# u4xVCA_v3.net
KiCad netlist of a schematic drawn in EAGLE
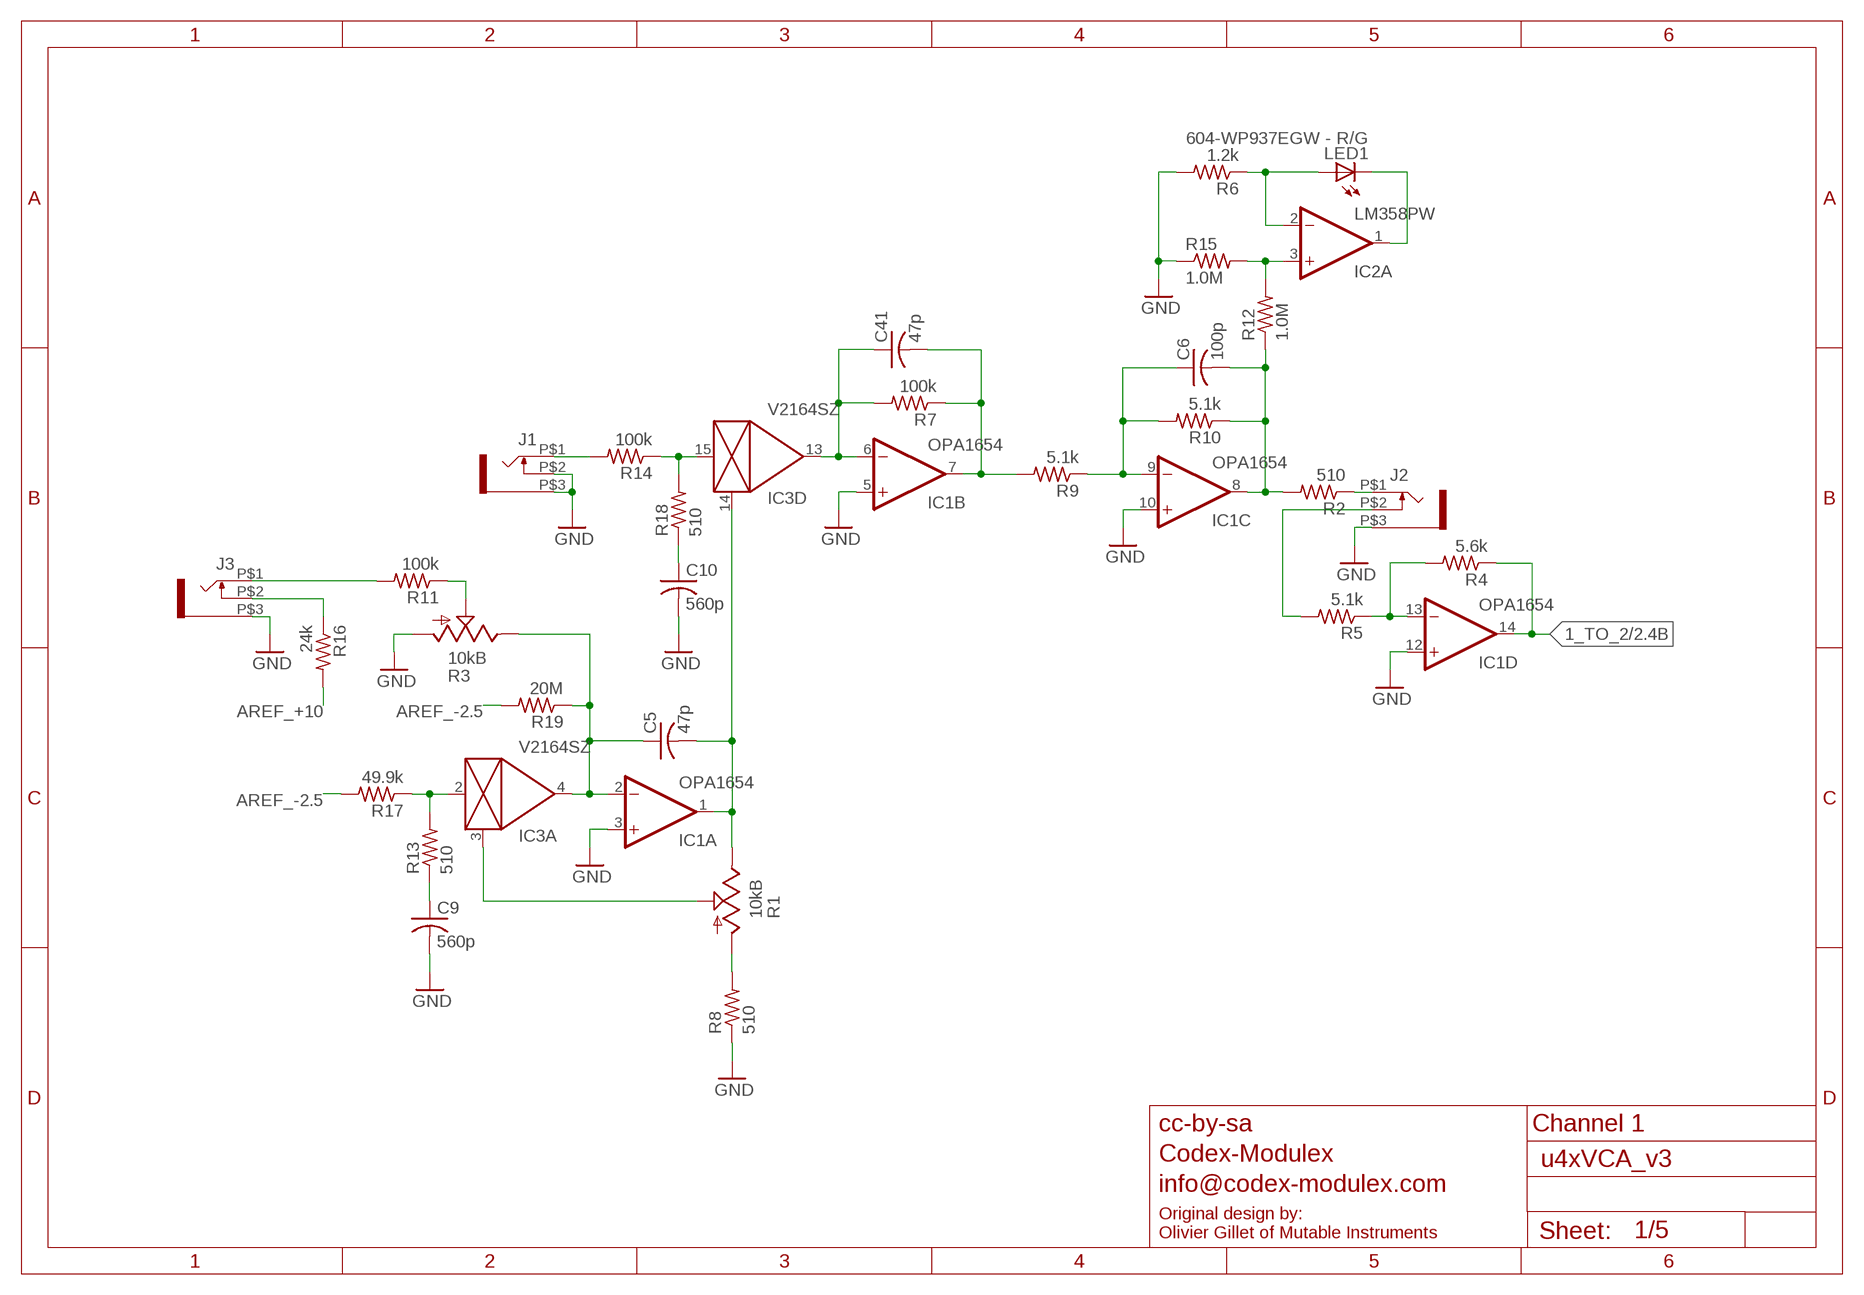
[diagram p0: schematic, sheet 1]
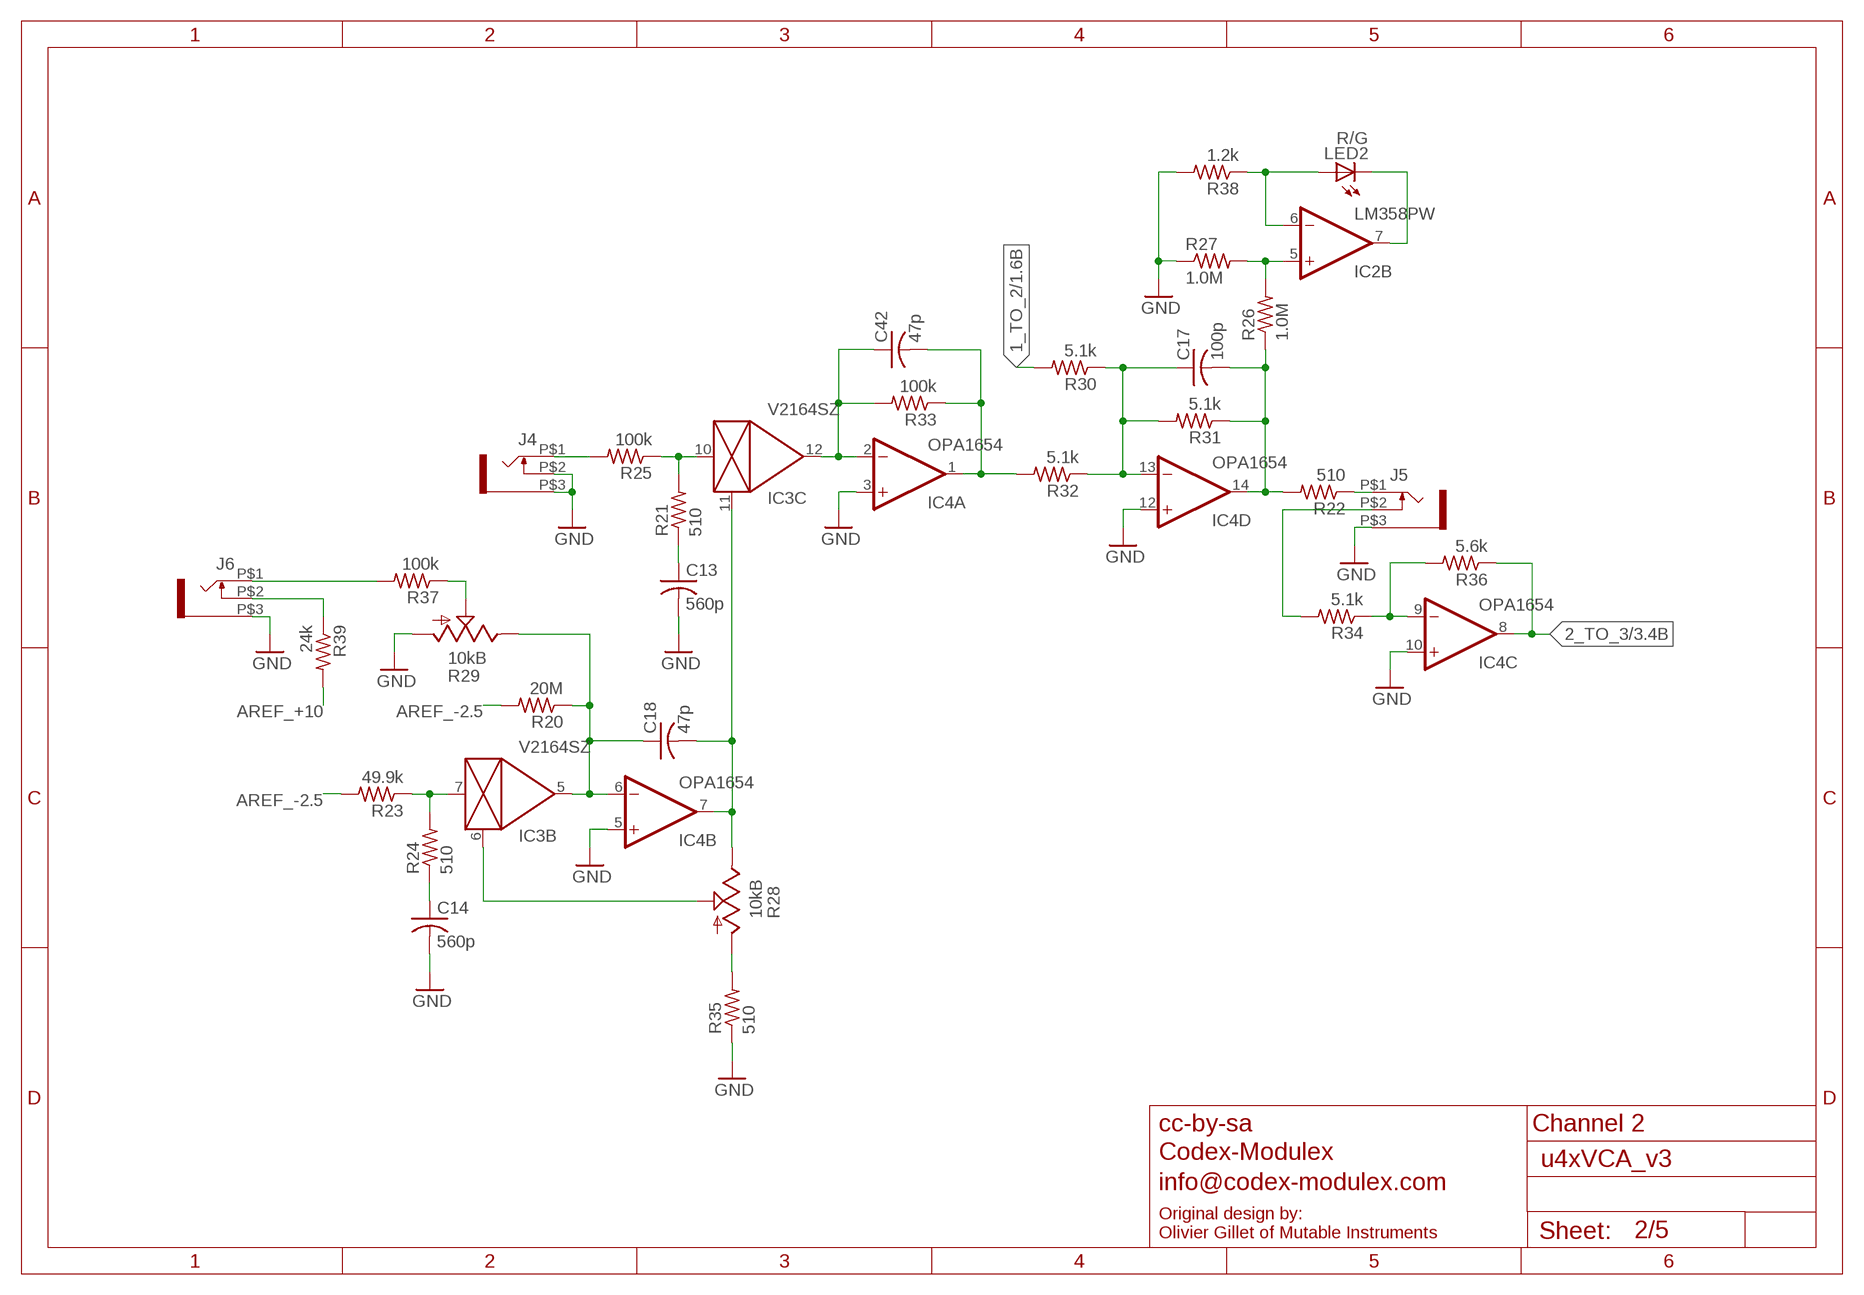
[diagram p1: schematic, sheet 2]
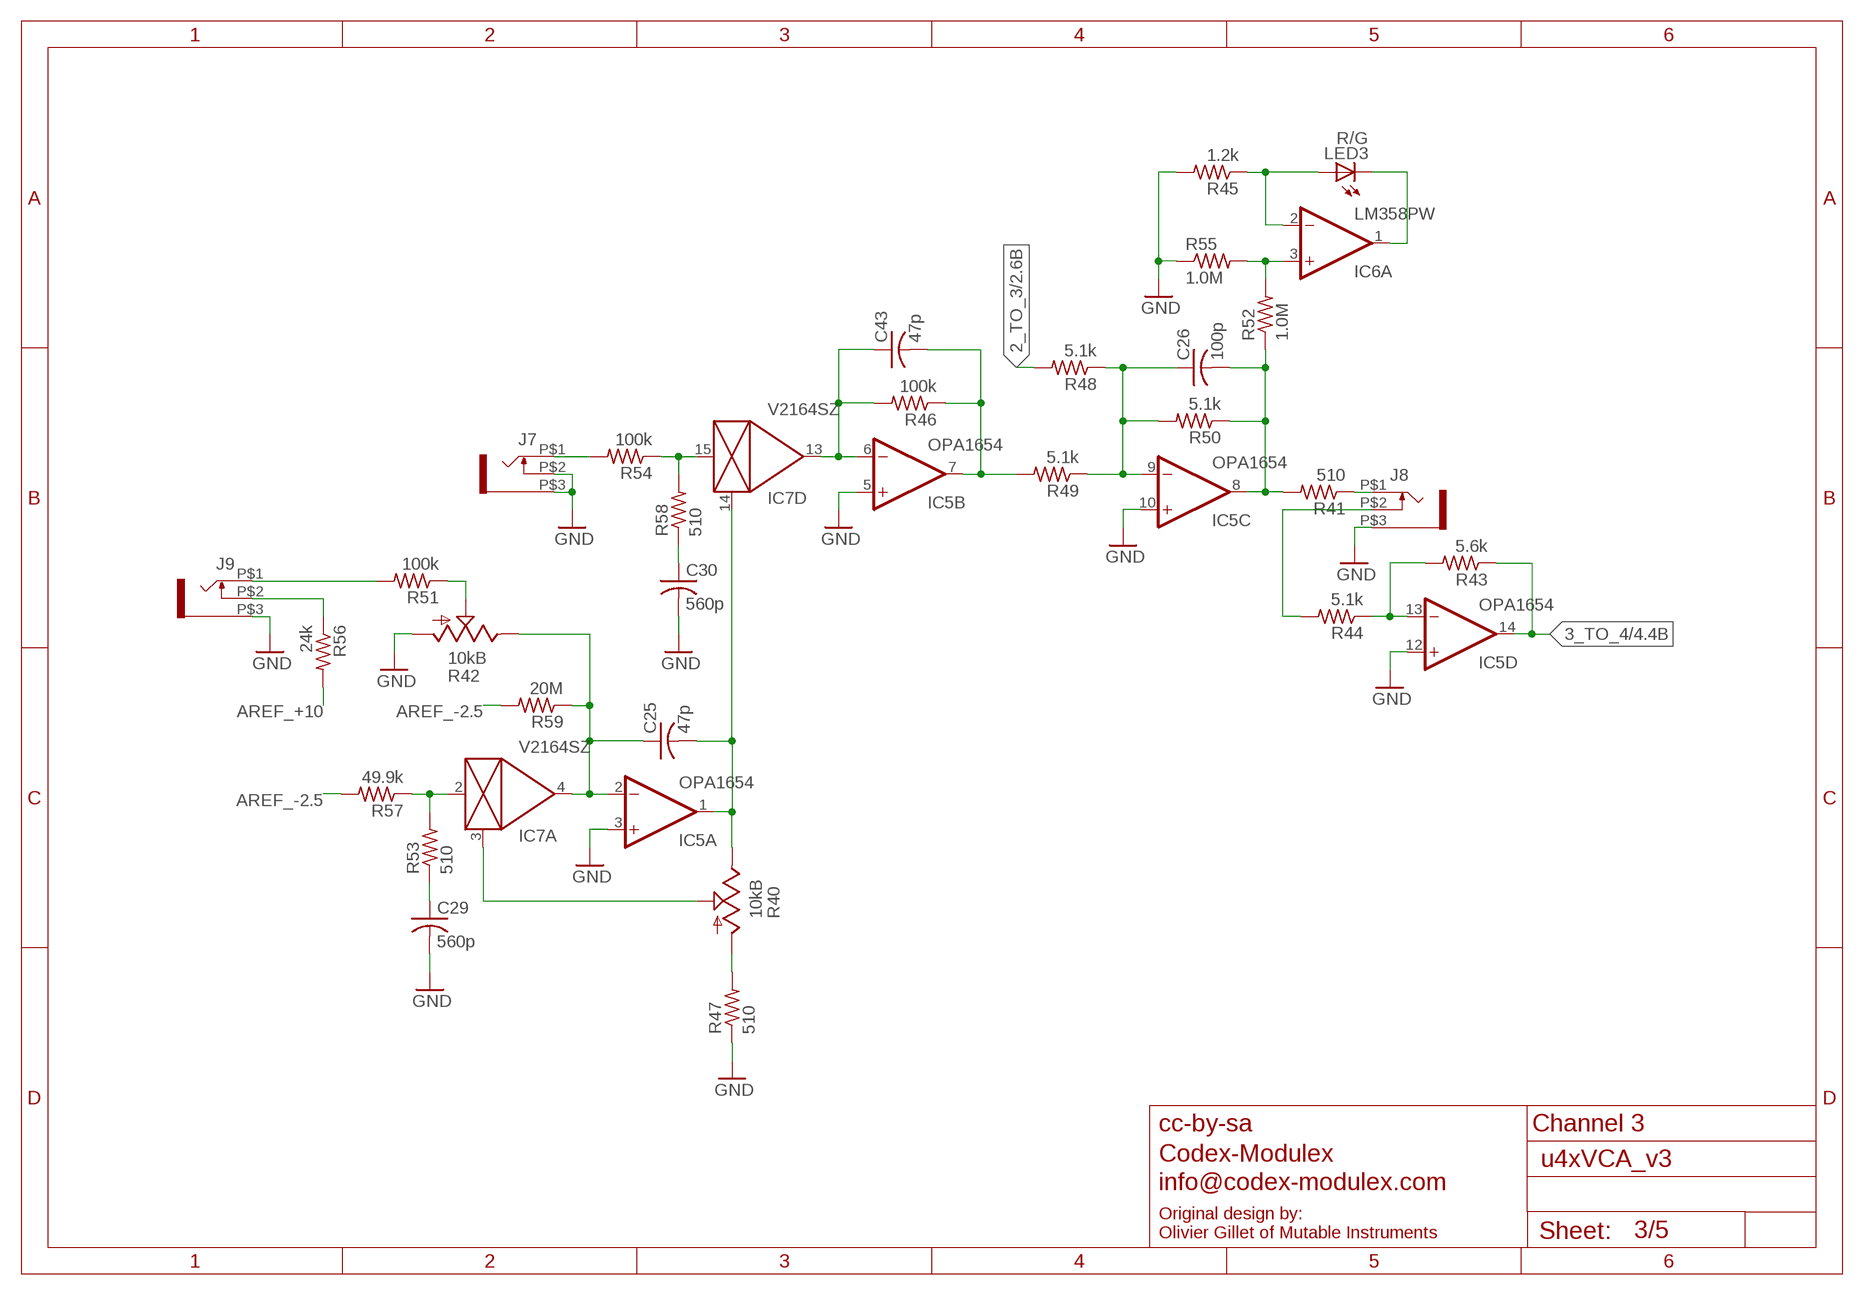
[diagram p2: schematic, sheet 3]
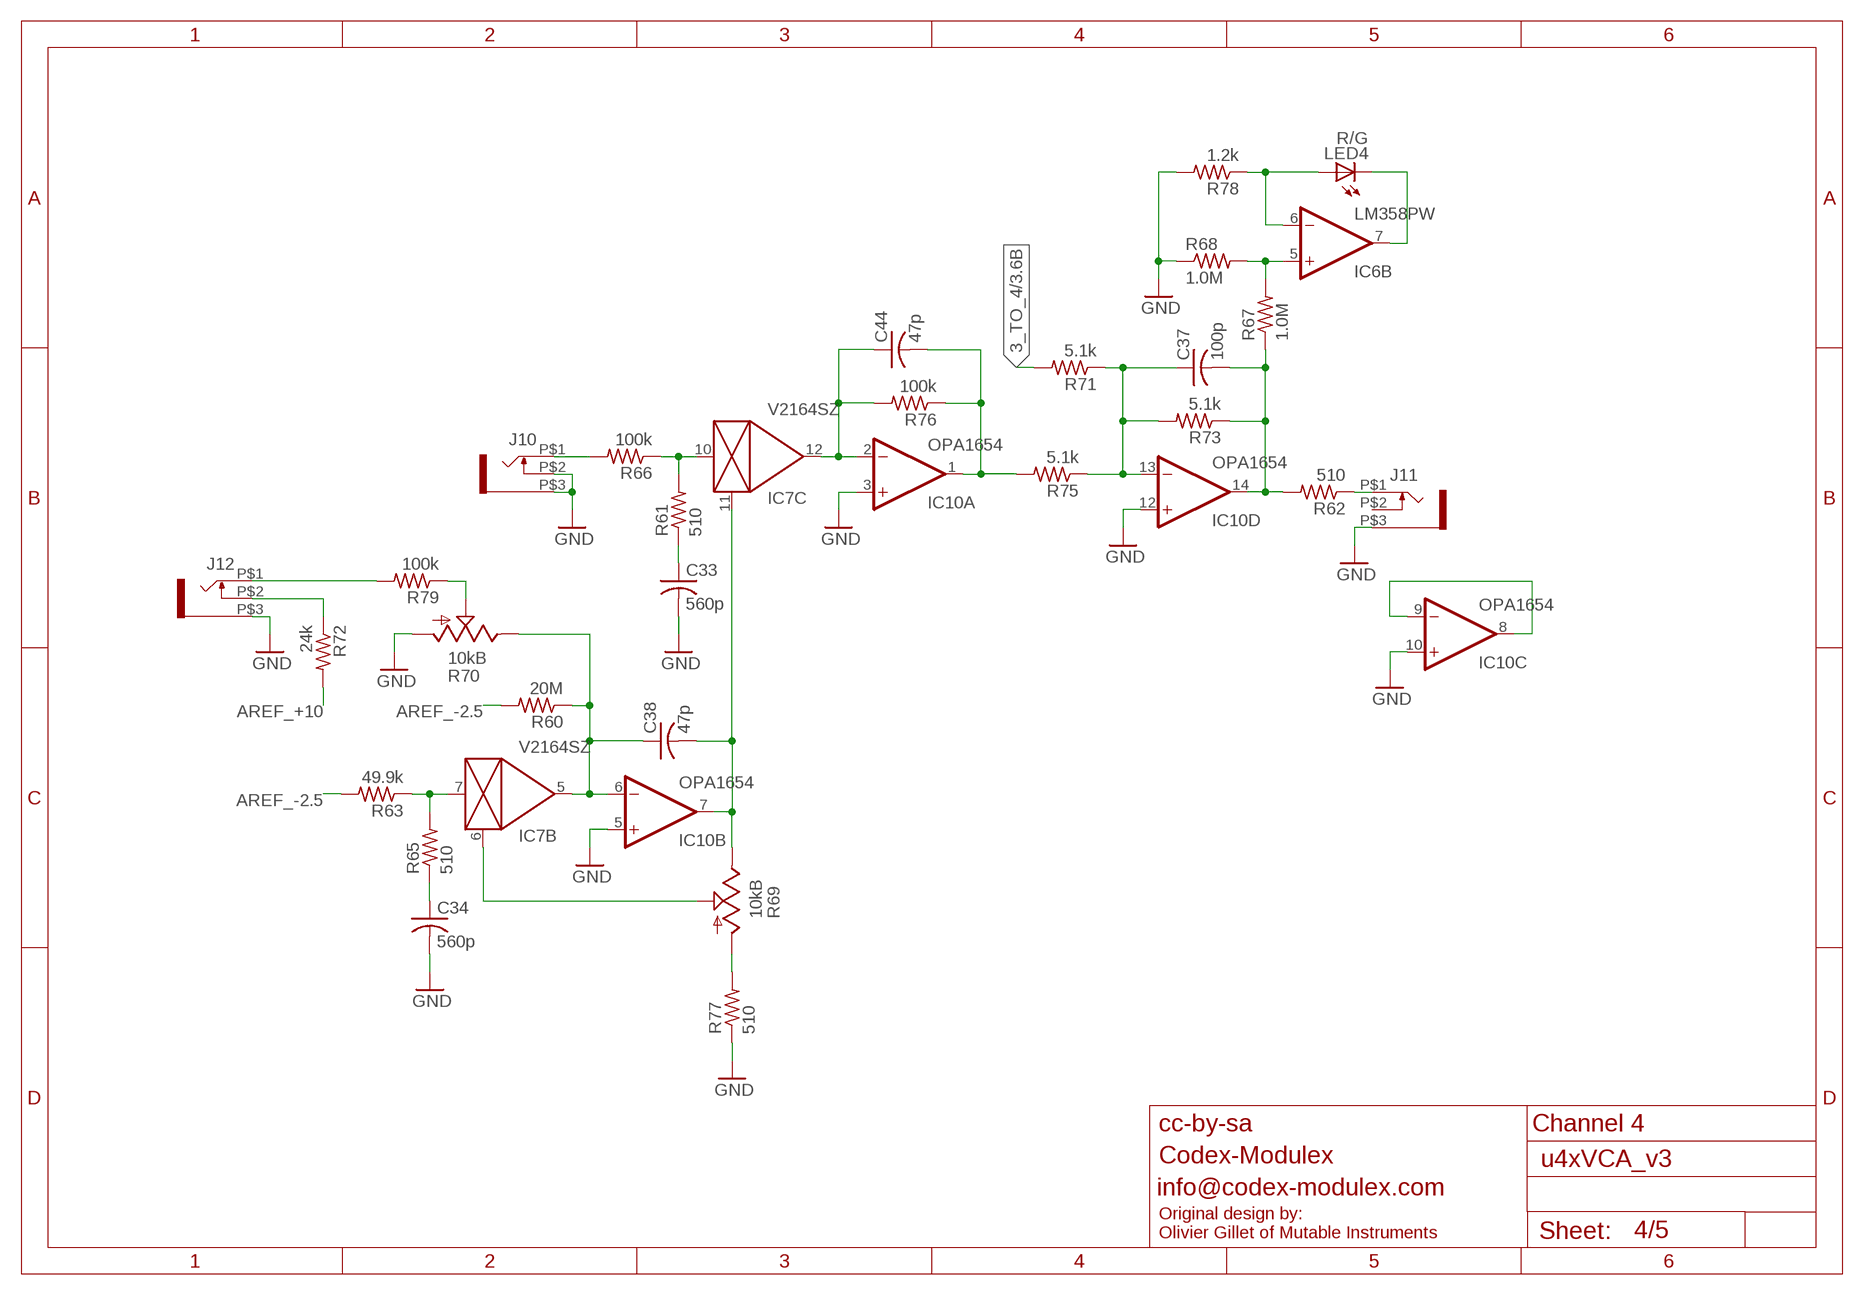
[diagram p3: schematic, sheet 4]
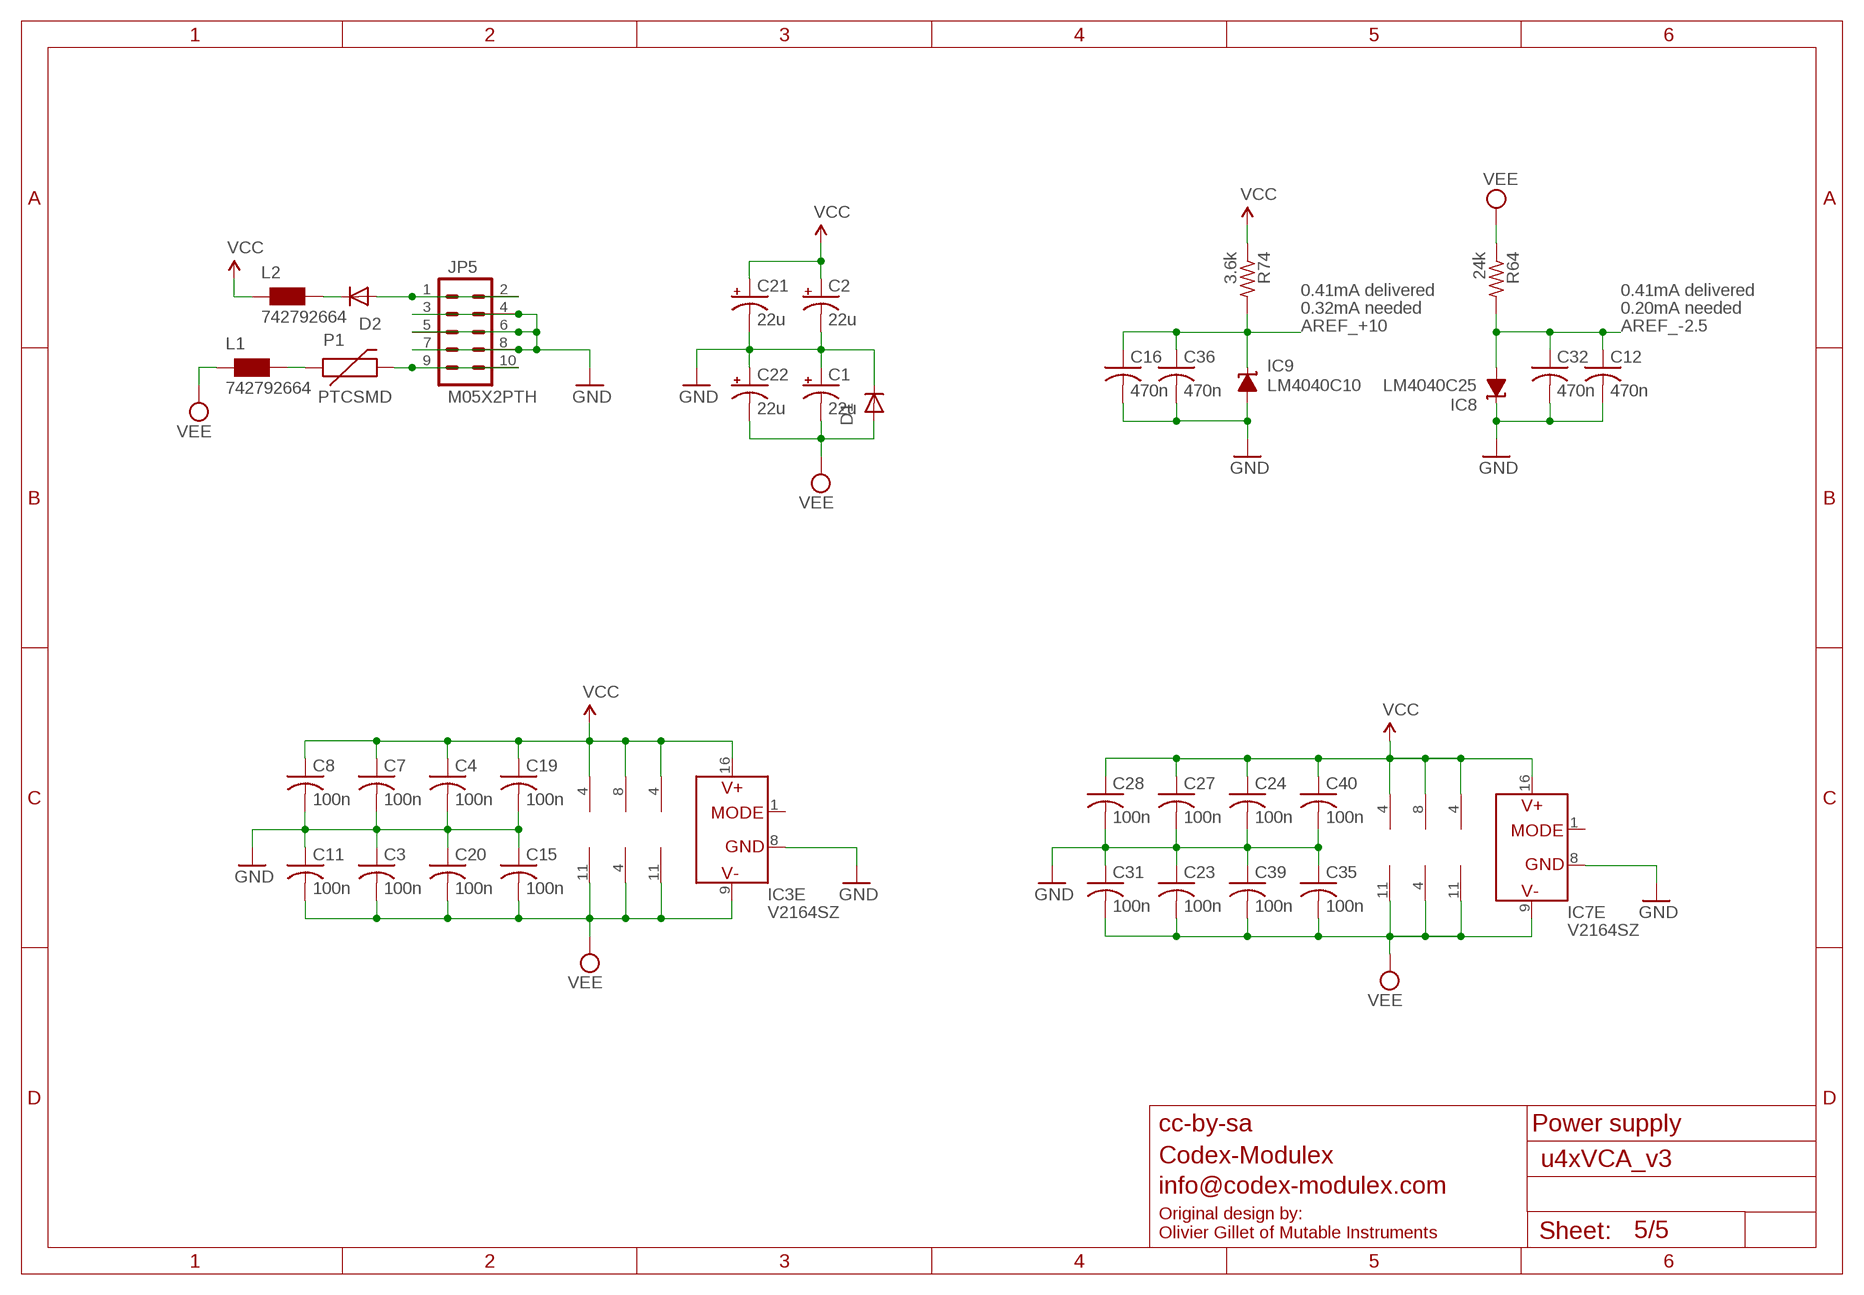
[diagram p4: schematic, sheet 5]

(export (version "E")
  (design (tool "Eeschema 10.0.6"))
  (components
    (comp (ref "C1")
      (value "22u")
      (footprint "eagle-import:PANASONIC_B")
      (libsource (lib "eagle-import") (part "CPOL-USB"))
    )
    (comp (ref "C2")
      (value "22u")
      (footprint "eagle-import:PANASONIC_B")
      (libsource (lib "eagle-import") (part "CPOL-USB"))
    )
    (comp (ref "C3")
      (value "100n")
      (footprint "eagle-import:C0603")
      (libsource (lib "eagle-import") (part "C-USC0603"))
    )
    (comp (ref "C4")
      (value "100n")
      (footprint "eagle-import:C0603")
      (libsource (lib "eagle-import") (part "C-USC0603"))
    )
    (comp (ref "C7")
      (value "100n")
      (footprint "eagle-import:C0603")
      (libsource (lib "eagle-import") (part "C-USC0603"))
    )
    (comp (ref "C8")
      (value "100n")
      (footprint "eagle-import:C0603")
      (libsource (lib "eagle-import") (part "C-USC0603"))
    )
    (comp (ref "C11")
      (value "100n")
      (footprint "eagle-import:C0603")
      (libsource (lib "eagle-import") (part "C-USC0603"))
    )
    (comp (ref "C12")
      (value "470n")
      (footprint "eagle-import:C0603")
      (libsource (lib "eagle-import") (part "C-USC0603"))
    )
    (comp (ref "C15")
      (value "100n")
      (footprint "eagle-import:C0603")
      (libsource (lib "eagle-import") (part "C-USC0603"))
    )
    (comp (ref "C16")
      (value "470n")
      (footprint "eagle-import:C0603")
      (libsource (lib "eagle-import") (part "C-USC0603"))
    )
    (comp (ref "C19")
      (value "100n")
      (footprint "eagle-import:C0603")
      (libsource (lib "eagle-import") (part "C-USC0603"))
    )
    (comp (ref "C20")
      (value "100n")
      (footprint "eagle-import:C0603")
      (libsource (lib "eagle-import") (part "C-USC0603"))
    )
    (comp (ref "C21")
      (value "22u")
      (footprint "eagle-import:PANASONIC_B")
      (libsource (lib "eagle-import") (part "CPOL-USB"))
    )
    (comp (ref "C22")
      (value "22u")
      (footprint "eagle-import:PANASONIC_B")
      (libsource (lib "eagle-import") (part "CPOL-USB"))
    )
    (comp (ref "C23")
      (value "100n")
      (footprint "eagle-import:C0603")
      (libsource (lib "eagle-import") (part "C-USC0603"))
    )
    (comp (ref "C24")
      (value "100n")
      (footprint "eagle-import:C0603")
      (libsource (lib "eagle-import") (part "C-USC0603"))
    )
    (comp (ref "C27")
      (value "100n")
      (footprint "eagle-import:C0603")
      (libsource (lib "eagle-import") (part "C-USC0603"))
    )
    (comp (ref "C28")
      (value "100n")
      (footprint "eagle-import:C0603")
      (libsource (lib "eagle-import") (part "C-USC0603"))
    )
    (comp (ref "C31")
      (value "100n")
      (footprint "eagle-import:C0603")
      (libsource (lib "eagle-import") (part "C-USC0603"))
    )
    (comp (ref "C32")
      (value "470n")
      (footprint "eagle-import:C0603")
      (libsource (lib "eagle-import") (part "C-USC0603"))
    )
    (comp (ref "C35")
      (value "100n")
      (footprint "eagle-import:C0603")
      (libsource (lib "eagle-import") (part "C-USC0603"))
    )
    (comp (ref "C36")
      (value "470n")
      (footprint "eagle-import:C0603")
      (libsource (lib "eagle-import") (part "C-USC0603"))
    )
    (comp (ref "C39")
      (value "100n")
      (footprint "eagle-import:C0603")
      (libsource (lib "eagle-import") (part "C-USC0603"))
    )
    (comp (ref "C40")
      (value "100n")
      (footprint "eagle-import:C0603")
      (libsource (lib "eagle-import") (part "C-USC0603"))
    )
    (comp (ref "D1")
      (value "1N5819HW")
      (footprint "eagle-import:SOD123")
      (libsource (lib "eagle-import") (part "DIODE-SOD123"))
    )
    (comp (ref "D2")
      (value "1N5819HW")
      (footprint "eagle-import:SOD123")
      (libsource (lib "eagle-import") (part "DIODE-SOD123"))
    )
    (comp (ref "IC1")
      (value "OPA1654")
      (footprint "eagle-import:TSSOP14")
      (libsource (lib "eagle-import") (part "TL074PW"))
    )
    (comp (ref "IC2")
      (value "LM358PW")
      (footprint "eagle-import:TSSOP8")
      (libsource (lib "eagle-import") (part "TL072PW"))
    )
    (comp (ref "IC3")
      (value "V2164SZ")
      (footprint "eagle-import:SOIC16N")
      (libsource (lib "eagle-import") (part "SSM2164S"))
    )
    (comp (ref "IC4")
      (value "OPA1654")
      (footprint "eagle-import:TSSOP14")
      (libsource (lib "eagle-import") (part "TL074PW"))
    )
    (comp (ref "IC5")
      (value "OPA1654")
      (footprint "eagle-import:TSSOP14")
      (libsource (lib "eagle-import") (part "TL074PW"))
    )
    (comp (ref "IC6")
      (value "LM358PW")
      (footprint "eagle-import:TSSOP8")
      (libsource (lib "eagle-import") (part "TL072PW"))
    )
    (comp (ref "IC7")
      (value "V2164SZ")
      (footprint "eagle-import:SOIC16N")
      (libsource (lib "eagle-import") (part "SSM2164S"))
    )
    (comp (ref "IC8")
      (value "LM4040C25")
      (footprint "eagle-import:DBZ_R-PDSO-G3")
      (libsource (lib "eagle-import") (part "LM4041DBZB12"))
    )
    (comp (ref "IC9")
      (value "LM4040C10")
      (footprint "eagle-import:DBZ_R-PDSO-G3")
      (libsource (lib "eagle-import") (part "LM4041DBZB12"))
    )
    (comp (ref "IC10")
      (value "OPA1654")
      (footprint "eagle-import:TSSOP14")
      (libsource (lib "eagle-import") (part "TL074PW"))
    )
    (comp (ref "JP5")
      (value "M05X2PTH")
      (footprint "eagle-import:AVR_ICSP")
      (libsource (lib "eagle-import") (part "M05X2PTH"))
    )
    (comp (ref "L1")
      (value "742792664")
      (footprint "eagle-import:0603")
      (libsource (lib "eagle-import") (part "WE-CBF_0603"))
    )
    (comp (ref "L2")
      (value "742792664")
      (footprint "eagle-import:0603")
      (libsource (lib "eagle-import") (part "WE-CBF_0603"))
    )
    (comp (ref "P1")
      (value "PTCSMD")
      (footprint "eagle-import:PTC-1206")
      (libsource (lib "eagle-import") (part "PTCSMD"))
    )
    (comp (ref "R64")
      (value "24k")
      (footprint "eagle-import:PARTS_AMAN_RESISTOR_0603")
      (libsource (lib "eagle-import") (part "PARTS_AMAN_RESISTOR"))
    )
    (comp (ref "R74")
      (value "3.6k")
      (footprint "eagle-import:PARTS_AMAN_RESISTOR_0603")
      (libsource (lib "eagle-import") (part "PARTS_AMAN_RESISTOR"))
    )
    (comp (ref "C5")
      (value "47p")
      (footprint "eagle-import:C0603")
      (libsource (lib "eagle-import") (part "C-USC0603"))
    )
    (comp (ref "C6")
      (value "100p")
      (footprint "eagle-import:C0603")
      (libsource (lib "eagle-import") (part "C-USC0603"))
    )
    (comp (ref "C9")
      (value "560p")
      (footprint "eagle-import:C0603")
      (libsource (lib "eagle-import") (part "C-USC0603"))
    )
    (comp (ref "C10")
      (value "560p")
      (footprint "eagle-import:C0603")
      (libsource (lib "eagle-import") (part "C-USC0603"))
    )
    (comp (ref "C41")
      (value "47p")
      (footprint "eagle-import:C0603")
      (libsource (lib "eagle-import") (part "C-USC0603"))
    )
    (comp (ref "J1")
      (value "WQP-PJ301M-12_JACK")
      (footprint "eagle-import:WQP-PJ301M-12_JACK")
      (libsource (lib "eagle-import") (part "WQP-PJ301M-12_JACK"))
    )
    (comp (ref "J2")
      (value "WQP-PJ301M-12_JACK")
      (footprint "eagle-import:WQP-PJ301M-12_JACK")
      (libsource (lib "eagle-import") (part "WQP-PJ301M-12_JACK"))
    )
    (comp (ref "J3")
      (value "WQP-PJ301M-12_JACK")
      (footprint "eagle-import:WQP-PJ301M-12_JACK")
      (libsource (lib "eagle-import") (part "WQP-PJ301M-12_JACK"))
    )
    (comp (ref "LED1")
      (value "604-WP937EGW - R/G")
      (footprint "eagle-import:LED3MM")
      (libsource (lib "eagle-import") (part "LED3MM"))
    )
    (comp (ref "R1")
      (value "10kB")
      (footprint "eagle-import:ALPS_POT_VERTICAL")
      (libsource (lib "eagle-import") (part "POT_USVERTICAL"))
    )
    (comp (ref "R2")
      (value "510")
      (footprint "eagle-import:PARTS_AMAN_RESISTOR_0603")
      (libsource (lib "eagle-import") (part "PARTS_AMAN_RESISTOR"))
    )
    (comp (ref "R3")
      (value "10kB")
      (footprint "eagle-import:ALPS_POT_VERTICAL")
      (libsource (lib "eagle-import") (part "POT_USVERTICAL"))
    )
    (comp (ref "R4")
      (value "5.6k")
      (footprint "eagle-import:PARTS_AMAN_RESISTOR_0603")
      (libsource (lib "eagle-import") (part "PARTS_AMAN_RESISTOR"))
    )
    (comp (ref "R5")
      (value "5.1k")
      (footprint "eagle-import:PARTS_AMAN_RESISTOR_0603")
      (libsource (lib "eagle-import") (part "PARTS_AMAN_RESISTOR"))
    )
    (comp (ref "R6")
      (value "1.2k")
      (footprint "eagle-import:PARTS_AMAN_RESISTOR_0603")
      (libsource (lib "eagle-import") (part "PARTS_AMAN_RESISTOR"))
    )
    (comp (ref "R7")
      (value "100k")
      (footprint "eagle-import:PARTS_AMAN_RESISTOR_0603")
      (libsource (lib "eagle-import") (part "PARTS_AMAN_RESISTOR"))
    )
    (comp (ref "R8")
      (value "510")
      (footprint "eagle-import:R0603")
      (libsource (lib "eagle-import") (part "R-US_R0603"))
    )
    (comp (ref "R9")
      (value "5.1k")
      (footprint "eagle-import:PARTS_AMAN_RESISTOR_0603")
      (libsource (lib "eagle-import") (part "PARTS_AMAN_RESISTOR"))
    )
    (comp (ref "R10")
      (value "5.1k")
      (footprint "eagle-import:PARTS_AMAN_RESISTOR_0603")
      (libsource (lib "eagle-import") (part "PARTS_AMAN_RESISTOR"))
    )
    (comp (ref "R11")
      (value "100k")
      (footprint "eagle-import:PARTS_AMAN_RESISTOR_0603")
      (libsource (lib "eagle-import") (part "PARTS_AMAN_RESISTOR"))
    )
    (comp (ref "R12")
      (value "1.0M")
      (footprint "eagle-import:PARTS_AMAN_RESISTOR_0603")
      (libsource (lib "eagle-import") (part "PARTS_AMAN_RESISTOR"))
    )
    (comp (ref "R13")
      (value "510")
      (footprint "eagle-import:PARTS_AMAN_RESISTOR_0603")
      (libsource (lib "eagle-import") (part "PARTS_AMAN_RESISTOR"))
    )
    (comp (ref "R14")
      (value "100k")
      (footprint "eagle-import:PARTS_AMAN_RESISTOR_0603")
      (libsource (lib "eagle-import") (part "PARTS_AMAN_RESISTOR"))
    )
    (comp (ref "R15")
      (value "1.0M")
      (footprint "eagle-import:PARTS_AMAN_RESISTOR_0603")
      (libsource (lib "eagle-import") (part "PARTS_AMAN_RESISTOR"))
    )
    (comp (ref "R16")
      (value "24k")
      (footprint "eagle-import:PARTS_AMAN_RESISTOR_0603")
      (libsource (lib "eagle-import") (part "PARTS_AMAN_RESISTOR"))
    )
    (comp (ref "R17")
      (value "49.9k")
      (footprint "eagle-import:PARTS_AMAN_RESISTOR_0603")
      (libsource (lib "eagle-import") (part "PARTS_AMAN_RESISTOR"))
    )
    (comp (ref "R18")
      (value "510")
      (footprint "eagle-import:PARTS_AMAN_RESISTOR_0603")
      (libsource (lib "eagle-import") (part "PARTS_AMAN_RESISTOR"))
    )
    (comp (ref "R19")
      (value "20M")
      (footprint "eagle-import:PARTS_AMAN_RESISTOR_0603")
      (libsource (lib "eagle-import") (part "PARTS_AMAN_RESISTOR"))
    )
    (comp (ref "C25")
      (value "47p")
      (footprint "eagle-import:C0603")
      (libsource (lib "eagle-import") (part "C-USC0603"))
    )
    (comp (ref "C26")
      (value "100p")
      (footprint "eagle-import:C0603")
      (libsource (lib "eagle-import") (part "C-USC0603"))
    )
    (comp (ref "C29")
      (value "560p")
      (footprint "eagle-import:C0603")
      (libsource (lib "eagle-import") (part "C-USC0603"))
    )
    (comp (ref "C30")
      (value "560p")
      (footprint "eagle-import:C0603")
      (libsource (lib "eagle-import") (part "C-USC0603"))
    )
    (comp (ref "C43")
      (value "47p")
      (footprint "eagle-import:C0603")
      (libsource (lib "eagle-import") (part "C-USC0603"))
    )
    (comp (ref "J7")
      (value "WQP-PJ301M-12_JACK")
      (footprint "eagle-import:WQP-PJ301M-12_JACK")
      (libsource (lib "eagle-import") (part "WQP-PJ301M-12_JACK"))
    )
    (comp (ref "J8")
      (value "WQP-PJ301M-12_JACK")
      (footprint "eagle-import:WQP-PJ301M-12_JACK")
      (libsource (lib "eagle-import") (part "WQP-PJ301M-12_JACK"))
    )
    (comp (ref "J9")
      (value "WQP-PJ301M-12_JACK")
      (footprint "eagle-import:WQP-PJ301M-12_JACK")
      (libsource (lib "eagle-import") (part "WQP-PJ301M-12_JACK"))
    )
    (comp (ref "LED3")
      (value "R/G")
      (footprint "eagle-import:LED3MM")
      (libsource (lib "eagle-import") (part "LED3MM"))
    )
    (comp (ref "R40")
      (value "10kB")
      (footprint "eagle-import:ALPS_POT_VERTICAL")
      (libsource (lib "eagle-import") (part "POT_USVERTICAL"))
    )
    (comp (ref "R41")
      (value "510")
      (footprint "eagle-import:PARTS_AMAN_RESISTOR_0603")
      (libsource (lib "eagle-import") (part "PARTS_AMAN_RESISTOR"))
    )
    (comp (ref "R42")
      (value "10kB")
      (footprint "eagle-import:ALPS_POT_VERTICAL")
      (libsource (lib "eagle-import") (part "POT_USVERTICAL"))
    )
    (comp (ref "R43")
      (value "5.6k")
      (footprint "eagle-import:PARTS_AMAN_RESISTOR_0603")
      (libsource (lib "eagle-import") (part "PARTS_AMAN_RESISTOR"))
    )
    (comp (ref "R44")
      (value "5.1k")
      (footprint "eagle-import:PARTS_AMAN_RESISTOR_0603")
      (libsource (lib "eagle-import") (part "PARTS_AMAN_RESISTOR"))
    )
    (comp (ref "R45")
      (value "1.2k")
      (footprint "eagle-import:PARTS_AMAN_RESISTOR_0603")
      (libsource (lib "eagle-import") (part "PARTS_AMAN_RESISTOR"))
    )
    (comp (ref "R46")
      (value "100k")
      (footprint "eagle-import:PARTS_AMAN_RESISTOR_0603")
      (libsource (lib "eagle-import") (part "PARTS_AMAN_RESISTOR"))
    )
    (comp (ref "R47")
      (value "510")
      (footprint "eagle-import:PARTS_AMAN_RESISTOR_0603")
      (libsource (lib "eagle-import") (part "PARTS_AMAN_RESISTOR"))
    )
    (comp (ref "R48")
      (value "5.1k")
      (footprint "eagle-import:PARTS_AMAN_RESISTOR_0603")
      (libsource (lib "eagle-import") (part "PARTS_AMAN_RESISTOR"))
    )
    (comp (ref "R49")
      (value "5.1k")
      (footprint "eagle-import:PARTS_AMAN_RESISTOR_0603")
      (libsource (lib "eagle-import") (part "PARTS_AMAN_RESISTOR"))
    )
    (comp (ref "R50")
      (value "5.1k")
      (footprint "eagle-import:PARTS_AMAN_RESISTOR_0603")
      (libsource (lib "eagle-import") (part "PARTS_AMAN_RESISTOR"))
    )
    (comp (ref "R51")
      (value "100k")
      (footprint "eagle-import:PARTS_AMAN_RESISTOR_0603")
      (libsource (lib "eagle-import") (part "PARTS_AMAN_RESISTOR"))
    )
    (comp (ref "R52")
      (value "1.0M")
      (footprint "eagle-import:PARTS_AMAN_RESISTOR_0603")
      (libsource (lib "eagle-import") (part "PARTS_AMAN_RESISTOR"))
    )
    (comp (ref "R53")
      (value "510")
      (footprint "eagle-import:PARTS_AMAN_RESISTOR_0603")
      (libsource (lib "eagle-import") (part "PARTS_AMAN_RESISTOR"))
    )
    (comp (ref "R54")
      (value "100k")
      (footprint "eagle-import:PARTS_AMAN_RESISTOR_0603")
      (libsource (lib "eagle-import") (part "PARTS_AMAN_RESISTOR"))
    )
    (comp (ref "R55")
      (value "1.0M")
      (footprint "eagle-import:PARTS_AMAN_RESISTOR_0603")
      (libsource (lib "eagle-import") (part "PARTS_AMAN_RESISTOR"))
    )
    (comp (ref "R56")
      (value "24k")
      (footprint "eagle-import:PARTS_AMAN_RESISTOR_0603")
      (libsource (lib "eagle-import") (part "PARTS_AMAN_RESISTOR"))
    )
    (comp (ref "R57")
      (value "49.9k")
      (footprint "eagle-import:PARTS_AMAN_RESISTOR_0603")
      (libsource (lib "eagle-import") (part "PARTS_AMAN_RESISTOR"))
    )
    (comp (ref "R58")
      (value "510")
      (footprint "eagle-import:PARTS_AMAN_RESISTOR_0603")
      (libsource (lib "eagle-import") (part "PARTS_AMAN_RESISTOR"))
    )
    (comp (ref "R59")
      (value "20M")
      (footprint "eagle-import:PARTS_AMAN_RESISTOR_0603")
      (libsource (lib "eagle-import") (part "PARTS_AMAN_RESISTOR"))
    )
    (comp (ref "C13")
      (value "560p")
      (footprint "eagle-import:C0603")
      (libsource (lib "eagle-import") (part "C-USC0603"))
    )
    (comp (ref "C14")
      (value "560p")
      (footprint "eagle-import:C0603")
      (libsource (lib "eagle-import") (part "C-USC0603"))
    )
    (comp (ref "C17")
      (value "100p")
      (footprint "eagle-import:C0603")
      (libsource (lib "eagle-import") (part "C-USC0603"))
    )
    (comp (ref "C18")
      (value "47p")
      (footprint "eagle-import:C0603")
      (libsource (lib "eagle-import") (part "C-USC0603"))
    )
    (comp (ref "C42")
      (value "47p")
      (footprint "eagle-import:C0603")
      (libsource (lib "eagle-import") (part "C-USC0603"))
    )
    (comp (ref "J4")
      (value "WQP-PJ301M-12_JACK")
      (footprint "eagle-import:WQP-PJ301M-12_JACK")
      (libsource (lib "eagle-import") (part "WQP-PJ301M-12_JACK"))
    )
    (comp (ref "J5")
      (value "WQP-PJ301M-12_JACK")
      (footprint "eagle-import:WQP-PJ301M-12_JACK")
      (libsource (lib "eagle-import") (part "WQP-PJ301M-12_JACK"))
    )
    (comp (ref "J6")
      (value "WQP-PJ301M-12_JACK")
      (footprint "eagle-import:WQP-PJ301M-12_JACK")
      (libsource (lib "eagle-import") (part "WQP-PJ301M-12_JACK"))
    )
    (comp (ref "LED2")
      (value "R/G")
      (footprint "eagle-import:LED3MM")
      (libsource (lib "eagle-import") (part "LED3MM"))
    )
    (comp (ref "R20")
      (value "20M")
      (footprint "eagle-import:PARTS_AMAN_RESISTOR_0603")
      (libsource (lib "eagle-import") (part "PARTS_AMAN_RESISTOR"))
    )
    (comp (ref "R21")
      (value "510")
      (footprint "eagle-import:PARTS_AMAN_RESISTOR_0603")
      (libsource (lib "eagle-import") (part "PARTS_AMAN_RESISTOR"))
    )
    (comp (ref "R22")
      (value "510")
      (footprint "eagle-import:R0603")
      (libsource (lib "eagle-import") (part "R-US_R0603"))
    )
    (comp (ref "R23")
      (value "49.9k")
      (footprint "eagle-import:PARTS_AMAN_RESISTOR_0603")
      (libsource (lib "eagle-import") (part "PARTS_AMAN_RESISTOR"))
    )
    (comp (ref "R24")
      (value "510")
      (footprint "eagle-import:PARTS_AMAN_RESISTOR_0603")
      (libsource (lib "eagle-import") (part "PARTS_AMAN_RESISTOR"))
    )
    (comp (ref "R25")
      (value "100k")
      (footprint "eagle-import:PARTS_AMAN_RESISTOR_0603")
      (libsource (lib "eagle-import") (part "PARTS_AMAN_RESISTOR"))
    )
    (comp (ref "R26")
      (value "1.0M")
      (footprint "eagle-import:PARTS_AMAN_RESISTOR_0603")
      (libsource (lib "eagle-import") (part "PARTS_AMAN_RESISTOR"))
    )
    (comp (ref "R27")
      (value "1.0M")
      (footprint "eagle-import:PARTS_AMAN_RESISTOR_0603")
      (libsource (lib "eagle-import") (part "PARTS_AMAN_RESISTOR"))
    )
    (comp (ref "R28")
      (value "10kB")
      (footprint "eagle-import:ALPS_POT_VERTICAL")
      (libsource (lib "eagle-import") (part "POT_USVERTICAL"))
    )
    (comp (ref "R29")
      (value "10kB")
      (footprint "eagle-import:ALPS_POT_VERTICAL")
      (libsource (lib "eagle-import") (part "POT_USVERTICAL"))
    )
    (comp (ref "R30")
      (value "5.1k")
      (footprint "eagle-import:PARTS_AMAN_RESISTOR_0603")
      (libsource (lib "eagle-import") (part "PARTS_AMAN_RESISTOR"))
    )
    (comp (ref "R31")
      (value "5.1k")
      (footprint "eagle-import:PARTS_AMAN_RESISTOR_0603")
      (libsource (lib "eagle-import") (part "PARTS_AMAN_RESISTOR"))
    )
    (comp (ref "R32")
      (value "5.1k")
      (footprint "eagle-import:PARTS_AMAN_RESISTOR_0603")
      (libsource (lib "eagle-import") (part "PARTS_AMAN_RESISTOR"))
    )
    (comp (ref "R33")
      (value "100k")
      (footprint "eagle-import:PARTS_AMAN_RESISTOR_0603")
      (libsource (lib "eagle-import") (part "PARTS_AMAN_RESISTOR"))
    )
    (comp (ref "R34")
      (value "5.1k")
      (footprint "eagle-import:PARTS_AMAN_RESISTOR_0603")
      (libsource (lib "eagle-import") (part "PARTS_AMAN_RESISTOR"))
    )
    (comp (ref "R35")
      (value "510")
      (footprint "eagle-import:R0603")
      (libsource (lib "eagle-import") (part "R-US_R0603"))
    )
    (comp (ref "R36")
      (value "5.6k")
      (footprint "eagle-import:PARTS_AMAN_RESISTOR_0603")
      (libsource (lib "eagle-import") (part "PARTS_AMAN_RESISTOR"))
    )
    (comp (ref "R37")
      (value "100k")
      (footprint "eagle-import:PARTS_AMAN_RESISTOR_0603")
      (libsource (lib "eagle-import") (part "PARTS_AMAN_RESISTOR"))
    )
    (comp (ref "R38")
      (value "1.2k")
      (footprint "eagle-import:PARTS_AMAN_RESISTOR_0603")
      (libsource (lib "eagle-import") (part "PARTS_AMAN_RESISTOR"))
    )
    (comp (ref "R39")
      (value "24k")
      (footprint "eagle-import:PARTS_AMAN_RESISTOR_0603")
      (libsource (lib "eagle-import") (part "PARTS_AMAN_RESISTOR"))
    )
    (comp (ref "C33")
      (value "560p")
      (footprint "eagle-import:C0603")
      (libsource (lib "eagle-import") (part "C-USC0603"))
    )
    (comp (ref "C34")
      (value "560p")
      (footprint "eagle-import:C0603")
      (libsource (lib "eagle-import") (part "C-USC0603"))
    )
    (comp (ref "C37")
      (value "100p")
      (footprint "eagle-import:C0603")
      (libsource (lib "eagle-import") (part "C-USC0603"))
    )
    (comp (ref "C38")
      (value "47p")
      (footprint "eagle-import:C0603")
      (libsource (lib "eagle-import") (part "C-USC0603"))
    )
    (comp (ref "C44")
      (value "47p")
      (footprint "eagle-import:C0603")
      (libsource (lib "eagle-import") (part "C-USC0603"))
    )
    (comp (ref "J10")
      (value "WQP-PJ301M-12_JACK")
      (footprint "eagle-import:WQP-PJ301M-12_JACK")
      (libsource (lib "eagle-import") (part "WQP-PJ301M-12_JACK"))
    )
    (comp (ref "J11")
      (value "WQP-PJ301M-12_JACK")
      (footprint "eagle-import:WQP-PJ301M-12_JACK")
      (libsource (lib "eagle-import") (part "WQP-PJ301M-12_JACK"))
    )
    (comp (ref "J12")
      (value "WQP-PJ301M-12_JACK")
      (footprint "eagle-import:WQP-PJ301M-12_JACK")
      (libsource (lib "eagle-import") (part "WQP-PJ301M-12_JACK"))
    )
    (comp (ref "LED4")
      (value "R/G")
      (footprint "eagle-import:LED3MM")
      (libsource (lib "eagle-import") (part "LED3MM"))
    )
    (comp (ref "R60")
      (value "20M")
      (footprint "eagle-import:PARTS_AMAN_RESISTOR_0603")
      (libsource (lib "eagle-import") (part "PARTS_AMAN_RESISTOR"))
    )
    (comp (ref "R61")
      (value "510")
      (footprint "eagle-import:PARTS_AMAN_RESISTOR_0603")
      (libsource (lib "eagle-import") (part "PARTS_AMAN_RESISTOR"))
    )
    (comp (ref "R62")
      (value "510")
      (footprint "eagle-import:PARTS_AMAN_RESISTOR_0603")
      (libsource (lib "eagle-import") (part "PARTS_AMAN_RESISTOR"))
    )
    (comp (ref "R63")
      (value "49.9k")
      (footprint "eagle-import:PARTS_AMAN_RESISTOR_0603")
      (libsource (lib "eagle-import") (part "PARTS_AMAN_RESISTOR"))
    )
    (comp (ref "R65")
      (value "510")
      (footprint "eagle-import:PARTS_AMAN_RESISTOR_0603")
      (libsource (lib "eagle-import") (part "PARTS_AMAN_RESISTOR"))
    )
    (comp (ref "R66")
      (value "100k")
      (footprint "eagle-import:PARTS_AMAN_RESISTOR_0603")
      (libsource (lib "eagle-import") (part "PARTS_AMAN_RESISTOR"))
    )
    (comp (ref "R67")
      (value "1.0M")
      (footprint "eagle-import:PARTS_AMAN_RESISTOR_0603")
      (libsource (lib "eagle-import") (part "PARTS_AMAN_RESISTOR"))
    )
    (comp (ref "R68")
      (value "1.0M")
      (footprint "eagle-import:PARTS_AMAN_RESISTOR_0603")
      (libsource (lib "eagle-import") (part "PARTS_AMAN_RESISTOR"))
    )
    (comp (ref "R69")
      (value "10kB")
      (footprint "eagle-import:ALPS_POT_VERTICAL")
      (libsource (lib "eagle-import") (part "POT_USVERTICAL"))
    )
    (comp (ref "R70")
      (value "10kB")
      (footprint "eagle-import:ALPS_POT_VERTICAL")
      (libsource (lib "eagle-import") (part "POT_USVERTICAL"))
    )
    (comp (ref "R71")
      (value "5.1k")
      (footprint "eagle-import:PARTS_AMAN_RESISTOR_0603")
      (libsource (lib "eagle-import") (part "PARTS_AMAN_RESISTOR"))
    )
    (comp (ref "R72")
      (value "24k")
      (footprint "eagle-import:PARTS_AMAN_RESISTOR_0603")
      (libsource (lib "eagle-import") (part "PARTS_AMAN_RESISTOR"))
    )
    (comp (ref "R73")
      (value "5.1k")
      (footprint "eagle-import:PARTS_AMAN_RESISTOR_0603")
      (libsource (lib "eagle-import") (part "PARTS_AMAN_RESISTOR"))
    )
    (comp (ref "R75")
      (value "5.1k")
      (footprint "eagle-import:PARTS_AMAN_RESISTOR_0603")
      (libsource (lib "eagle-import") (part "PARTS_AMAN_RESISTOR"))
    )
    (comp (ref "R76")
      (value "100k")
      (footprint "eagle-import:PARTS_AMAN_RESISTOR_0603")
      (libsource (lib "eagle-import") (part "PARTS_AMAN_RESISTOR"))
    )
    (comp (ref "R77")
      (value "510")
      (footprint "eagle-import:PARTS_AMAN_RESISTOR_0603")
      (libsource (lib "eagle-import") (part "PARTS_AMAN_RESISTOR"))
    )
    (comp (ref "R78")
      (value "1.2k")
      (footprint "eagle-import:PARTS_AMAN_RESISTOR_0603")
      (libsource (lib "eagle-import") (part "PARTS_AMAN_RESISTOR"))
    )
    (comp (ref "R79")
      (value "100k")
      (footprint "eagle-import:PARTS_AMAN_RESISTOR_0603")
      (libsource (lib "eagle-import") (part "PARTS_AMAN_RESISTOR"))
    )
  )
  (nets
    (net (code "1") (name "1_TO_2") (class "Default")
      (node (ref "IC1") (pin "14") (pinfunction "OUT_14") (pintype "output"))
      (node (ref "R30") (pin "2") (pinfunction "2_2") (pintype "passive"))
      (node (ref "R4") (pin "1") (pinfunction "1_1") (pintype "passive"))
    )
    (net (code "2") (name "2_TO_3") (class "Default")
      (node (ref "IC4") (pin "8") (pinfunction "OUT_8") (pintype "output"))
      (node (ref "R36") (pin "1") (pinfunction "1_1") (pintype "passive"))
      (node (ref "R48") (pin "2") (pinfunction "2_2") (pintype "passive"))
    )
    (net (code "3") (name "3_TO_4") (class "Default")
      (node (ref "IC5") (pin "14") (pinfunction "OUT_14") (pintype "output"))
      (node (ref "R43") (pin "1") (pinfunction "1_1") (pintype "passive"))
      (node (ref "R71") (pin "2") (pinfunction "2_2") (pintype "passive"))
    )
    (net (code "4") (name "AREF_+10") (class "Default")
      (node (ref "C16") (pin "1") (pinfunction "1_1") (pintype "passive"))
      (node (ref "C36") (pin "1") (pinfunction "1_1") (pintype "passive"))
      (node (ref "IC9") (pin "1") (pinfunction "C_1") (pintype "passive"))
      (node (ref "R16") (pin "2") (pinfunction "2_2") (pintype "passive"))
      (node (ref "R39") (pin "2") (pinfunction "2_2") (pintype "passive"))
      (node (ref "R56") (pin "2") (pinfunction "2_2") (pintype "passive"))
      (node (ref "R72") (pin "2") (pinfunction "2_2") (pintype "passive"))
      (node (ref "R74") (pin "2") (pinfunction "2_2") (pintype "passive"))
    )
    (net (code "5") (name "AREF_-2.5") (class "Default")
      (node (ref "C12") (pin "1") (pinfunction "1_1") (pintype "passive"))
      (node (ref "C32") (pin "1") (pinfunction "1_1") (pintype "passive"))
      (node (ref "IC8") (pin "2") (pinfunction "A_2") (pintype "passive"))
      (node (ref "R17") (pin "2") (pinfunction "2_2") (pintype "passive"))
      (node (ref "R19") (pin "2") (pinfunction "2_2") (pintype "passive"))
      (node (ref "R20") (pin "2") (pinfunction "2_2") (pintype "passive"))
      (node (ref "R23") (pin "2") (pinfunction "2_2") (pintype "passive"))
      (node (ref "R57") (pin "2") (pinfunction "2_2") (pintype "passive"))
      (node (ref "R59") (pin "2") (pinfunction "2_2") (pintype "passive"))
      (node (ref "R60") (pin "2") (pinfunction "2_2") (pintype "passive"))
      (node (ref "R63") (pin "2") (pinfunction "2_2") (pintype "passive"))
      (node (ref "R64") (pin "2") (pinfunction "2_2") (pintype "passive"))
    )
    (net (code "6") (name "GND") (class "Default")
      (node (ref "C1") (pin "+") (pinfunction "+_+") (pintype "passive"))
      (node (ref "C10") (pin "2") (pinfunction "2_2") (pintype "passive"))
      (node (ref "C11") (pin "1") (pinfunction "1_1") (pintype "passive"))
      (node (ref "C12") (pin "2") (pinfunction "2_2") (pintype "passive"))
      (node (ref "C13") (pin "2") (pinfunction "2_2") (pintype "passive"))
      (node (ref "C14") (pin "2") (pinfunction "2_2") (pintype "passive"))
      (node (ref "C15") (pin "1") (pinfunction "1_1") (pintype "passive"))
      (node (ref "C16") (pin "2") (pinfunction "2_2") (pintype "passive"))
      (node (ref "C19") (pin "2") (pinfunction "2_2") (pintype "passive"))
      (node (ref "C2") (pin "-") (pinfunction "-_-") (pintype "passive"))
      (node (ref "C20") (pin "1") (pinfunction "1_1") (pintype "passive"))
      (node (ref "C21") (pin "-") (pinfunction "-_-") (pintype "passive"))
      (node (ref "C22") (pin "+") (pinfunction "+_+") (pintype "passive"))
      (node (ref "C23") (pin "1") (pinfunction "1_1") (pintype "passive"))
      (node (ref "C24") (pin "2") (pinfunction "2_2") (pintype "passive"))
      (node (ref "C27") (pin "2") (pinfunction "2_2") (pintype "passive"))
      (node (ref "C28") (pin "2") (pinfunction "2_2") (pintype "passive"))
      (node (ref "C29") (pin "2") (pinfunction "2_2") (pintype "passive"))
      (node (ref "C3") (pin "1") (pinfunction "1_1") (pintype "passive"))
      (node (ref "C30") (pin "2") (pinfunction "2_2") (pintype "passive"))
      (node (ref "C31") (pin "1") (pinfunction "1_1") (pintype "passive"))
      (node (ref "C32") (pin "2") (pinfunction "2_2") (pintype "passive"))
      (node (ref "C33") (pin "2") (pinfunction "2_2") (pintype "passive"))
      (node (ref "C34") (pin "2") (pinfunction "2_2") (pintype "passive"))
      (node (ref "C35") (pin "1") (pinfunction "1_1") (pintype "passive"))
      (node (ref "C36") (pin "2") (pinfunction "2_2") (pintype "passive"))
      (node (ref "C39") (pin "1") (pinfunction "1_1") (pintype "passive"))
      (node (ref "C4") (pin "2") (pinfunction "2_2") (pintype "passive"))
      (node (ref "C40") (pin "2") (pinfunction "2_2") (pintype "passive"))
      (node (ref "C7") (pin "2") (pinfunction "2_2") (pintype "passive"))
      (node (ref "C8") (pin "2") (pinfunction "2_2") (pintype "passive"))
      (node (ref "C9") (pin "2") (pinfunction "2_2") (pintype "passive"))
      (node (ref "D1") (pin "C") (pinfunction "C_C") (pintype "passive"))
      (node (ref "IC1") (pin "10") (pinfunction "+IN_10") (pintype "input"))
      (node (ref "IC1") (pin "12") (pinfunction "+IN_12") (pintype "input"))
      (node (ref "IC1") (pin "3") (pinfunction "+IN_3") (pintype "input"))
      (node (ref "IC1") (pin "5") (pinfunction "+IN_5") (pintype "input"))
      (node (ref "IC10") (pin "10") (pinfunction "+IN_10") (pintype "input"))
      (node (ref "IC10") (pin "12") (pinfunction "+IN_12") (pintype "input"))
      (node (ref "IC10") (pin "3") (pinfunction "+IN_3") (pintype "input"))
      (node (ref "IC10") (pin "5") (pinfunction "+IN_5") (pintype "input"))
      (node (ref "IC3") (pin "8") (pinfunction "GND_8") (pintype "power_in"))
      (node (ref "IC4") (pin "10") (pinfunction "+IN_10") (pintype "input"))
      (node (ref "IC4") (pin "12") (pinfunction "+IN_12") (pintype "input"))
      (node (ref "IC4") (pin "3") (pinfunction "+IN_3") (pintype "input"))
      (node (ref "IC4") (pin "5") (pinfunction "+IN_5") (pintype "input"))
      (node (ref "IC5") (pin "10") (pinfunction "+IN_10") (pintype "input"))
      (node (ref "IC5") (pin "12") (pinfunction "+IN_12") (pintype "input"))
      (node (ref "IC5") (pin "3") (pinfunction "+IN_3") (pintype "input"))
      (node (ref "IC5") (pin "5") (pinfunction "+IN_5") (pintype "input"))
      (node (ref "IC7") (pin "8") (pinfunction "GND_8") (pintype "power_in"))
      (node (ref "IC8") (pin "1") (pinfunction "C_1") (pintype "passive"))
      (node (ref "IC9") (pin "2") (pinfunction "A_2") (pintype "passive"))
      (node (ref "J1") (pin "P$2") (pinfunction "3_P$2") (pintype "passive"))
      (node (ref "J1") (pin "P$3") (pinfunction "1_P$3") (pintype "passive"))
      (node (ref "J10") (pin "P$2") (pinfunction "3_P$2") (pintype "passive"))
      (node (ref "J10") (pin "P$3") (pinfunction "1_P$3") (pintype "passive"))
      (node (ref "J11") (pin "P$3") (pinfunction "1_P$3") (pintype "passive"))
      (node (ref "J12") (pin "P$3") (pinfunction "1_P$3") (pintype "passive"))
      (node (ref "J2") (pin "P$3") (pinfunction "1_P$3") (pintype "passive"))
      (node (ref "J3") (pin "P$3") (pinfunction "1_P$3") (pintype "passive"))
      (node (ref "J4") (pin "P$2") (pinfunction "3_P$2") (pintype "passive"))
      (node (ref "J4") (pin "P$3") (pinfunction "1_P$3") (pintype "passive"))
      (node (ref "J5") (pin "P$3") (pinfunction "1_P$3") (pintype "passive"))
      (node (ref "J6") (pin "P$3") (pinfunction "1_P$3") (pintype "passive"))
      (node (ref "J7") (pin "P$2") (pinfunction "3_P$2") (pintype "passive"))
      (node (ref "J7") (pin "P$3") (pinfunction "1_P$3") (pintype "passive"))
      (node (ref "J8") (pin "P$3") (pinfunction "1_P$3") (pintype "passive"))
      (node (ref "J9") (pin "P$3") (pinfunction "1_P$3") (pintype "passive"))
      (node (ref "JP5") (pin "3") (pinfunction "3_3") (pintype "passive"))
      (node (ref "JP5") (pin "4") (pinfunction "4_4") (pintype "passive"))
      (node (ref "JP5") (pin "5") (pinfunction "5_5") (pintype "passive"))
      (node (ref "JP5") (pin "6") (pinfunction "6_6") (pintype "passive"))
      (node (ref "JP5") (pin "7") (pinfunction "7_7") (pintype "passive"))
      (node (ref "JP5") (pin "8") (pinfunction "8_8") (pintype "passive"))
      (node (ref "R15") (pin "1") (pinfunction "1_1") (pintype "passive"))
      (node (ref "R27") (pin "1") (pinfunction "1_1") (pintype "passive"))
      (node (ref "R29") (pin "P$3") (pinfunction "A_P$3") (pintype "passive"))
      (node (ref "R3") (pin "P$3") (pinfunction "A_P$3") (pintype "passive"))
      (node (ref "R35") (pin "1") (pinfunction "1_1") (pintype "passive"))
      (node (ref "R38") (pin "2") (pinfunction "2_2") (pintype "passive"))
      (node (ref "R42") (pin "P$3") (pinfunction "A_P$3") (pintype "passive"))
      (node (ref "R45") (pin "2") (pinfunction "2_2") (pintype "passive"))
      (node (ref "R47") (pin "1") (pinfunction "1_1") (pintype "passive"))
      (node (ref "R55") (pin "1") (pinfunction "1_1") (pintype "passive"))
      (node (ref "R6") (pin "2") (pinfunction "2_2") (pintype "passive"))
      (node (ref "R68") (pin "1") (pinfunction "1_1") (pintype "passive"))
      (node (ref "R70") (pin "P$3") (pinfunction "A_P$3") (pintype "passive"))
      (node (ref "R77") (pin "1") (pinfunction "1_1") (pintype "passive"))
      (node (ref "R78") (pin "2") (pinfunction "2_2") (pintype "passive"))
      (node (ref "R8") (pin "1") (pinfunction "1_1") (pintype "passive"))
    )
    (net (code "7") (name "Net-(C9-Pad1)") (class "Default")
      (node (ref "C9") (pin "1") (pinfunction "1_1") (pintype "passive"))
      (node (ref "R13") (pin "1") (pinfunction "1_1") (pintype "passive"))
    )
    (net (code "8") (name "Net-(C10-Pad1)") (class "Default")
      (node (ref "C10") (pin "1") (pinfunction "1_1") (pintype "passive"))
      (node (ref "R18") (pin "1") (pinfunction "1_1") (pintype "passive"))
    )
    (net (code "9") (name "Net-(C13-Pad1)") (class "Default")
      (node (ref "C13") (pin "1") (pinfunction "1_1") (pintype "passive"))
      (node (ref "R21") (pin "1") (pinfunction "1_1") (pintype "passive"))
    )
    (net (code "10") (name "Net-(C14-Pad1)") (class "Default")
      (node (ref "C14") (pin "1") (pinfunction "1_1") (pintype "passive"))
      (node (ref "R24") (pin "1") (pinfunction "1_1") (pintype "passive"))
    )
    (net (code "11") (name "Net-(C29-Pad1)") (class "Default")
      (node (ref "C29") (pin "1") (pinfunction "1_1") (pintype "passive"))
      (node (ref "R53") (pin "1") (pinfunction "1_1") (pintype "passive"))
    )
    (net (code "12") (name "Net-(C30-Pad1)") (class "Default")
      (node (ref "C30") (pin "1") (pinfunction "1_1") (pintype "passive"))
      (node (ref "R58") (pin "1") (pinfunction "1_1") (pintype "passive"))
    )
    (net (code "13") (name "Net-(C33-Pad1)") (class "Default")
      (node (ref "C33") (pin "1") (pinfunction "1_1") (pintype "passive"))
      (node (ref "R61") (pin "1") (pinfunction "1_1") (pintype "passive"))
    )
    (net (code "14") (name "Net-(C34-Pad1)") (class "Default")
      (node (ref "C34") (pin "1") (pinfunction "1_1") (pintype "passive"))
      (node (ref "R65") (pin "1") (pinfunction "1_1") (pintype "passive"))
    )
    (net (code "15") (name "Net-(D2-PadA)") (class "Default")
      (node (ref "D2") (pin "A") (pinfunction "A_A") (pintype "passive"))
      (node (ref "JP5") (pin "1") (pinfunction "1_1") (pintype "passive"))
      (node (ref "JP5") (pin "2") (pinfunction "2_2") (pintype "passive"))
    )
    (net (code "16") (name "Net-(D2-PadC)") (class "Default")
      (node (ref "D2") (pin "C") (pinfunction "C_C") (pintype "passive"))
      (node (ref "L2") (pin "2") (pinfunction "2_2") (pintype "passive"))
    )
    (net (code "17") (name "Net-(IC1A--IN)") (class "Default")
      (node (ref "C5") (pin "1") (pinfunction "1_1") (pintype "passive"))
      (node (ref "IC1") (pin "2") (pinfunction "-IN_2") (pintype "input"))
      (node (ref "IC3") (pin "4") (pinfunction "OUT_4") (pintype "output"))
      (node (ref "R19") (pin "1") (pinfunction "1_1") (pintype "passive"))
      (node (ref "R3") (pin "P$1") (pinfunction "E_P$1") (pintype "passive"))
    )
    (net (code "18") (name "Net-(IC1A-OUT)") (class "Default")
      (node (ref "C5") (pin "2") (pinfunction "2_2") (pintype "passive"))
      (node (ref "IC1") (pin "1") (pinfunction "OUT_1") (pintype "output"))
      (node (ref "IC3") (pin "14") (pinfunction "CTRL_14") (pintype "input"))
      (node (ref "R1") (pin "P$1") (pinfunction "E_P$1") (pintype "passive"))
    )
    (net (code "19") (name "Net-(IC1B--IN)") (class "Default")
      (node (ref "C41") (pin "1") (pinfunction "1_1") (pintype "passive"))
      (node (ref "IC1") (pin "6") (pinfunction "-IN_6") (pintype "input"))
      (node (ref "IC3") (pin "13") (pinfunction "OUT_13") (pintype "output"))
      (node (ref "R7") (pin "2") (pinfunction "2_2") (pintype "passive"))
    )
    (net (code "20") (name "Net-(IC1B-OUT)") (class "Default")
      (node (ref "C41") (pin "2") (pinfunction "2_2") (pintype "passive"))
      (node (ref "IC1") (pin "7") (pinfunction "OUT_7") (pintype "output"))
      (node (ref "R7") (pin "1") (pinfunction "1_1") (pintype "passive"))
      (node (ref "R9") (pin "2") (pinfunction "2_2") (pintype "passive"))
    )
    (net (code "21") (name "Net-(IC1C--IN)") (class "Default")
      (node (ref "C6") (pin "1") (pinfunction "1_1") (pintype "passive"))
      (node (ref "IC1") (pin "9") (pinfunction "-IN_9") (pintype "input"))
      (node (ref "R10") (pin "2") (pinfunction "2_2") (pintype "passive"))
      (node (ref "R9") (pin "1") (pinfunction "1_1") (pintype "passive"))
    )
    (net (code "22") (name "Net-(IC1C-OUT)") (class "Default")
      (node (ref "C6") (pin "2") (pinfunction "2_2") (pintype "passive"))
      (node (ref "IC1") (pin "8") (pinfunction "OUT_8") (pintype "output"))
      (node (ref "R10") (pin "1") (pinfunction "1_1") (pintype "passive"))
      (node (ref "R12") (pin "1") (pinfunction "1_1") (pintype "passive"))
      (node (ref "R2") (pin "2") (pinfunction "2_2") (pintype "passive"))
    )
    (net (code "23") (name "Net-(IC1D--IN)") (class "Default")
      (node (ref "IC1") (pin "13") (pinfunction "-IN_13") (pintype "input"))
      (node (ref "R4") (pin "2") (pinfunction "2_2") (pintype "passive"))
      (node (ref "R5") (pin "1") (pinfunction "1_1") (pintype "passive"))
    )
    (net (code "24") (name "Net-(IC2A-+IN)") (class "Default")
      (node (ref "IC2") (pin "3") (pinfunction "+IN_3") (pintype "input"))
      (node (ref "R12") (pin "2") (pinfunction "2_2") (pintype "passive"))
      (node (ref "R15") (pin "2") (pinfunction "2_2") (pintype "passive"))
    )
    (net (code "25") (name "Net-(IC2A--IN)") (class "Default")
      (node (ref "IC2") (pin "2") (pinfunction "-IN_2") (pintype "input"))
      (node (ref "LED1") (pin "A") (pinfunction "A_A") (pintype "passive"))
      (node (ref "R6") (pin "1") (pinfunction "1_1") (pintype "passive"))
    )
    (net (code "26") (name "Net-(IC2A-OUT)") (class "Default")
      (node (ref "IC2") (pin "1") (pinfunction "OUT_1") (pintype "output"))
      (node (ref "LED1") (pin "K") (pinfunction "C_K") (pintype "passive"))
    )
    (net (code "27") (name "Net-(IC2B-+IN)") (class "Default")
      (node (ref "IC2") (pin "5") (pinfunction "+IN_5") (pintype "input"))
      (node (ref "R26") (pin "2") (pinfunction "2_2") (pintype "passive"))
      (node (ref "R27") (pin "2") (pinfunction "2_2") (pintype "passive"))
    )
    (net (code "28") (name "Net-(IC2B--IN)") (class "Default")
      (node (ref "IC2") (pin "6") (pinfunction "-IN_6") (pintype "input"))
      (node (ref "LED2") (pin "A") (pinfunction "A_A") (pintype "passive"))
      (node (ref "R38") (pin "1") (pinfunction "1_1") (pintype "passive"))
    )
    (net (code "29") (name "Net-(IC2B-OUT)") (class "Default")
      (node (ref "IC2") (pin "7") (pinfunction "OUT_7") (pintype "output"))
      (node (ref "LED2") (pin "K") (pinfunction "C_K") (pintype "passive"))
    )
    (net (code "30") (name "Net-(IC3A-CTRL)") (class "Default")
      (node (ref "IC3") (pin "3") (pinfunction "CTRL_3") (pintype "input"))
      (node (ref "R1") (pin "P$2") (pinfunction "S_P$2") (pintype "passive"))
    )
    (net (code "31") (name "Net-(IC3A-IN)") (class "Default")
      (node (ref "IC3") (pin "2") (pinfunction "IN_2") (pintype "input"))
      (node (ref "R13") (pin "2") (pinfunction "2_2") (pintype "passive"))
      (node (ref "R17") (pin "1") (pinfunction "1_1") (pintype "passive"))
    )
    (net (code "32") (name "Net-(IC3B-CTRL)") (class "Default")
      (node (ref "IC3") (pin "6") (pinfunction "CTRL_6") (pintype "input"))
      (node (ref "R28") (pin "P$2") (pinfunction "S_P$2") (pintype "passive"))
    )
    (net (code "33") (name "Net-(IC3B-IN)") (class "Default")
      (node (ref "IC3") (pin "7") (pinfunction "IN_7") (pintype "input"))
      (node (ref "R23") (pin "1") (pinfunction "1_1") (pintype "passive"))
      (node (ref "R24") (pin "2") (pinfunction "2_2") (pintype "passive"))
    )
    (net (code "34") (name "Net-(IC3B-OUT)") (class "Default")
      (node (ref "C18") (pin "1") (pinfunction "1_1") (pintype "passive"))
      (node (ref "IC3") (pin "5") (pinfunction "OUT_5") (pintype "output"))
      (node (ref "IC4") (pin "6") (pinfunction "-IN_6") (pintype "input"))
      (node (ref "R20") (pin "1") (pinfunction "1_1") (pintype "passive"))
      (node (ref "R29") (pin "P$1") (pinfunction "E_P$1") (pintype "passive"))
    )
    (net (code "35") (name "Net-(IC3C-CTRL)") (class "Default")
      (node (ref "C18") (pin "2") (pinfunction "2_2") (pintype "passive"))
      (node (ref "IC3") (pin "11") (pinfunction "CTRL_11") (pintype "input"))
      (node (ref "IC4") (pin "7") (pinfunction "OUT_7") (pintype "output"))
      (node (ref "R28") (pin "P$1") (pinfunction "E_P$1") (pintype "passive"))
    )
    (net (code "36") (name "Net-(IC3C-IN)") (class "Default")
      (node (ref "IC3") (pin "10") (pinfunction "IN_10") (pintype "input"))
      (node (ref "R21") (pin "2") (pinfunction "2_2") (pintype "passive"))
      (node (ref "R25") (pin "1") (pinfunction "1_1") (pintype "passive"))
    )
    (net (code "37") (name "Net-(IC3C-OUT)") (class "Default")
      (node (ref "C42") (pin "1") (pinfunction "1_1") (pintype "passive"))
      (node (ref "IC3") (pin "12") (pinfunction "OUT_12") (pintype "output"))
      (node (ref "IC4") (pin "2") (pinfunction "-IN_2") (pintype "input"))
      (node (ref "R33") (pin "2") (pinfunction "2_2") (pintype "passive"))
    )
    (net (code "38") (name "Net-(IC3D-IN)") (class "Default")
      (node (ref "IC3") (pin "15") (pinfunction "IN_15") (pintype "input"))
      (node (ref "R14") (pin "1") (pinfunction "1_1") (pintype "passive"))
      (node (ref "R18") (pin "2") (pinfunction "2_2") (pintype "passive"))
    )
    (net (code "39") (name "Net-(IC4A-OUT)") (class "Default")
      (node (ref "C42") (pin "2") (pinfunction "2_2") (pintype "passive"))
      (node (ref "IC4") (pin "1") (pinfunction "OUT_1") (pintype "output"))
      (node (ref "R32") (pin "2") (pinfunction "2_2") (pintype "passive"))
      (node (ref "R33") (pin "1") (pinfunction "1_1") (pintype "passive"))
    )
    (net (code "40") (name "Net-(IC4C--IN)") (class "Default")
      (node (ref "IC4") (pin "9") (pinfunction "-IN_9") (pintype "input"))
      (node (ref "R34") (pin "1") (pinfunction "1_1") (pintype "passive"))
      (node (ref "R36") (pin "2") (pinfunction "2_2") (pintype "passive"))
    )
    (net (code "41") (name "Net-(IC4D--IN)") (class "Default")
      (node (ref "C17") (pin "1") (pinfunction "1_1") (pintype "passive"))
      (node (ref "IC4") (pin "13") (pinfunction "-IN_13") (pintype "input"))
      (node (ref "R30") (pin "1") (pinfunction "1_1") (pintype "passive"))
      (node (ref "R31") (pin "2") (pinfunction "2_2") (pintype "passive"))
      (node (ref "R32") (pin "1") (pinfunction "1_1") (pintype "passive"))
    )
    (net (code "42") (name "Net-(IC4D-OUT)") (class "Default")
      (node (ref "C17") (pin "2") (pinfunction "2_2") (pintype "passive"))
      (node (ref "IC4") (pin "14") (pinfunction "OUT_14") (pintype "output"))
      (node (ref "R22") (pin "2") (pinfunction "2_2") (pintype "passive"))
      (node (ref "R26") (pin "1") (pinfunction "1_1") (pintype "passive"))
      (node (ref "R31") (pin "1") (pinfunction "1_1") (pintype "passive"))
    )
    (net (code "43") (name "Net-(IC5A--IN)") (class "Default")
      (node (ref "C25") (pin "1") (pinfunction "1_1") (pintype "passive"))
      (node (ref "IC5") (pin "2") (pinfunction "-IN_2") (pintype "input"))
      (node (ref "IC7") (pin "4") (pinfunction "OUT_4") (pintype "output"))
      (node (ref "R42") (pin "P$1") (pinfunction "E_P$1") (pintype "passive"))
      (node (ref "R59") (pin "1") (pinfunction "1_1") (pintype "passive"))
    )
    (net (code "44") (name "Net-(IC5A-OUT)") (class "Default")
      (node (ref "C25") (pin "2") (pinfunction "2_2") (pintype "passive"))
      (node (ref "IC5") (pin "1") (pinfunction "OUT_1") (pintype "output"))
      (node (ref "IC7") (pin "14") (pinfunction "CTRL_14") (pintype "input"))
      (node (ref "R40") (pin "P$1") (pinfunction "E_P$1") (pintype "passive"))
    )
    (net (code "45") (name "Net-(IC5B--IN)") (class "Default")
      (node (ref "C43") (pin "1") (pinfunction "1_1") (pintype "passive"))
      (node (ref "IC5") (pin "6") (pinfunction "-IN_6") (pintype "input"))
      (node (ref "IC7") (pin "13") (pinfunction "OUT_13") (pintype "output"))
      (node (ref "R46") (pin "2") (pinfunction "2_2") (pintype "passive"))
    )
    (net (code "46") (name "Net-(IC5B-OUT)") (class "Default")
      (node (ref "C43") (pin "2") (pinfunction "2_2") (pintype "passive"))
      (node (ref "IC5") (pin "7") (pinfunction "OUT_7") (pintype "output"))
      (node (ref "R46") (pin "1") (pinfunction "1_1") (pintype "passive"))
      (node (ref "R49") (pin "2") (pinfunction "2_2") (pintype "passive"))
    )
    (net (code "47") (name "Net-(IC5C--IN)") (class "Default")
      (node (ref "C26") (pin "1") (pinfunction "1_1") (pintype "passive"))
      (node (ref "IC5") (pin "9") (pinfunction "-IN_9") (pintype "input"))
      (node (ref "R48") (pin "1") (pinfunction "1_1") (pintype "passive"))
      (node (ref "R49") (pin "1") (pinfunction "1_1") (pintype "passive"))
      (node (ref "R50") (pin "2") (pinfunction "2_2") (pintype "passive"))
    )
    (net (code "48") (name "Net-(IC5C-OUT)") (class "Default")
      (node (ref "C26") (pin "2") (pinfunction "2_2") (pintype "passive"))
      (node (ref "IC5") (pin "8") (pinfunction "OUT_8") (pintype "output"))
      (node (ref "R41") (pin "2") (pinfunction "2_2") (pintype "passive"))
      (node (ref "R50") (pin "1") (pinfunction "1_1") (pintype "passive"))
      (node (ref "R52") (pin "1") (pinfunction "1_1") (pintype "passive"))
    )
    (net (code "49") (name "Net-(IC5D--IN)") (class "Default")
      (node (ref "IC5") (pin "13") (pinfunction "-IN_13") (pintype "input"))
      (node (ref "R43") (pin "2") (pinfunction "2_2") (pintype "passive"))
      (node (ref "R44") (pin "1") (pinfunction "1_1") (pintype "passive"))
    )
    (net (code "50") (name "Net-(IC6A-+IN)") (class "Default")
      (node (ref "IC6") (pin "3") (pinfunction "+IN_3") (pintype "input"))
      (node (ref "R52") (pin "2") (pinfunction "2_2") (pintype "passive"))
      (node (ref "R55") (pin "2") (pinfunction "2_2") (pintype "passive"))
    )
    (net (code "51") (name "Net-(IC6A--IN)") (class "Default")
      (node (ref "IC6") (pin "2") (pinfunction "-IN_2") (pintype "input"))
      (node (ref "LED3") (pin "A") (pinfunction "A_A") (pintype "passive"))
      (node (ref "R45") (pin "1") (pinfunction "1_1") (pintype "passive"))
    )
    (net (code "52") (name "Net-(IC6A-OUT)") (class "Default")
      (node (ref "IC6") (pin "1") (pinfunction "OUT_1") (pintype "output"))
      (node (ref "LED3") (pin "K") (pinfunction "C_K") (pintype "passive"))
    )
    (net (code "53") (name "Net-(IC6B-+IN)") (class "Default")
      (node (ref "IC6") (pin "5") (pinfunction "+IN_5") (pintype "input"))
      (node (ref "R67") (pin "2") (pinfunction "2_2") (pintype "passive"))
      (node (ref "R68") (pin "2") (pinfunction "2_2") (pintype "passive"))
    )
    (net (code "54") (name "Net-(IC6B--IN)") (class "Default")
      (node (ref "IC6") (pin "6") (pinfunction "-IN_6") (pintype "input"))
      (node (ref "LED4") (pin "A") (pinfunction "A_A") (pintype "passive"))
      (node (ref "R78") (pin "1") (pinfunction "1_1") (pintype "passive"))
    )
    (net (code "55") (name "Net-(IC6B-OUT)") (class "Default")
      (node (ref "IC6") (pin "7") (pinfunction "OUT_7") (pintype "output"))
      (node (ref "LED4") (pin "K") (pinfunction "C_K") (pintype "passive"))
    )
    (net (code "56") (name "Net-(IC7A-CTRL)") (class "Default")
      (node (ref "IC7") (pin "3") (pinfunction "CTRL_3") (pintype "input"))
      (node (ref "R40") (pin "P$2") (pinfunction "S_P$2") (pintype "passive"))
    )
    (net (code "57") (name "Net-(IC7A-IN)") (class "Default")
      (node (ref "IC7") (pin "2") (pinfunction "IN_2") (pintype "input"))
      (node (ref "R53") (pin "2") (pinfunction "2_2") (pintype "passive"))
      (node (ref "R57") (pin "1") (pinfunction "1_1") (pintype "passive"))
    )
    (net (code "58") (name "Net-(IC7B-CTRL)") (class "Default")
      (node (ref "IC7") (pin "6") (pinfunction "CTRL_6") (pintype "input"))
      (node (ref "R69") (pin "P$2") (pinfunction "S_P$2") (pintype "passive"))
    )
    (net (code "59") (name "Net-(IC7B-IN)") (class "Default")
      (node (ref "IC7") (pin "7") (pinfunction "IN_7") (pintype "input"))
      (node (ref "R63") (pin "1") (pinfunction "1_1") (pintype "passive"))
      (node (ref "R65") (pin "2") (pinfunction "2_2") (pintype "passive"))
    )
    (net (code "60") (name "Net-(IC7C-IN)") (class "Default")
      (node (ref "IC7") (pin "10") (pinfunction "IN_10") (pintype "input"))
      (node (ref "R61") (pin "2") (pinfunction "2_2") (pintype "passive"))
      (node (ref "R66") (pin "1") (pinfunction "1_1") (pintype "passive"))
    )
    (net (code "61") (name "Net-(IC7D-IN)") (class "Default")
      (node (ref "IC7") (pin "15") (pinfunction "IN_15") (pintype "input"))
      (node (ref "R54") (pin "1") (pinfunction "1_1") (pintype "passive"))
      (node (ref "R58") (pin "2") (pinfunction "2_2") (pintype "passive"))
    )
    (net (code "62") (name "Net-(IC10A--IN)") (class "Default")
      (node (ref "C44") (pin "1") (pinfunction "1_1") (pintype "passive"))
      (node (ref "IC10") (pin "2") (pinfunction "-IN_2") (pintype "input"))
      (node (ref "IC7") (pin "12") (pinfunction "OUT_12") (pintype "output"))
      (node (ref "R76") (pin "2") (pinfunction "2_2") (pintype "passive"))
    )
    (net (code "63") (name "Net-(IC10A-OUT)") (class "Default")
      (node (ref "C44") (pin "2") (pinfunction "2_2") (pintype "passive"))
      (node (ref "IC10") (pin "1") (pinfunction "OUT_1") (pintype "output"))
      (node (ref "R75") (pin "2") (pinfunction "2_2") (pintype "passive"))
      (node (ref "R76") (pin "1") (pinfunction "1_1") (pintype "passive"))
    )
    (net (code "64") (name "Net-(IC10B--IN)") (class "Default")
      (node (ref "C38") (pin "1") (pinfunction "1_1") (pintype "passive"))
      (node (ref "IC10") (pin "6") (pinfunction "-IN_6") (pintype "input"))
      (node (ref "IC7") (pin "5") (pinfunction "OUT_5") (pintype "output"))
      (node (ref "R60") (pin "1") (pinfunction "1_1") (pintype "passive"))
      (node (ref "R70") (pin "P$1") (pinfunction "E_P$1") (pintype "passive"))
    )
    (net (code "65") (name "Net-(IC10B-OUT)") (class "Default")
      (node (ref "C38") (pin "2") (pinfunction "2_2") (pintype "passive"))
      (node (ref "IC10") (pin "7") (pinfunction "OUT_7") (pintype "output"))
      (node (ref "IC7") (pin "11") (pinfunction "CTRL_11") (pintype "input"))
      (node (ref "R69") (pin "P$1") (pinfunction "E_P$1") (pintype "passive"))
    )
    (net (code "66") (name "Net-(IC10C--IN)") (class "Default")
      (node (ref "IC10") (pin "8") (pinfunction "OUT_8") (pintype "output"))
      (node (ref "IC10") (pin "9") (pinfunction "-IN_9") (pintype "input"))
    )
    (net (code "67") (name "Net-(IC10D--IN)") (class "Default")
      (node (ref "C37") (pin "1") (pinfunction "1_1") (pintype "passive"))
      (node (ref "IC10") (pin "13") (pinfunction "-IN_13") (pintype "input"))
      (node (ref "R71") (pin "1") (pinfunction "1_1") (pintype "passive"))
      (node (ref "R73") (pin "2") (pinfunction "2_2") (pintype "passive"))
      (node (ref "R75") (pin "1") (pinfunction "1_1") (pintype "passive"))
    )
    (net (code "68") (name "Net-(IC10D-OUT)") (class "Default")
      (node (ref "C37") (pin "2") (pinfunction "2_2") (pintype "passive"))
      (node (ref "IC10") (pin "14") (pinfunction "OUT_14") (pintype "output"))
      (node (ref "R62") (pin "2") (pinfunction "2_2") (pintype "passive"))
      (node (ref "R67") (pin "1") (pinfunction "1_1") (pintype "passive"))
      (node (ref "R73") (pin "1") (pinfunction "1_1") (pintype "passive"))
    )
    (net (code "69") (name "Net-(J1-2)") (class "Default")
      (node (ref "J1") (pin "P$1") (pinfunction "2_P$1") (pintype "passive"))
      (node (ref "R14") (pin "2") (pinfunction "2_2") (pintype "passive"))
    )
    (net (code "70") (name "Net-(J2-2)") (class "Default")
      (node (ref "J2") (pin "P$1") (pinfunction "2_P$1") (pintype "passive"))
      (node (ref "R2") (pin "1") (pinfunction "1_1") (pintype "passive"))
    )
    (net (code "71") (name "Net-(J2-3)") (class "Default")
      (node (ref "J2") (pin "P$2") (pinfunction "3_P$2") (pintype "passive"))
      (node (ref "R5") (pin "2") (pinfunction "2_2") (pintype "passive"))
    )
    (net (code "72") (name "Net-(J3-2)") (class "Default")
      (node (ref "J3") (pin "P$1") (pinfunction "2_P$1") (pintype "passive"))
      (node (ref "R11") (pin "2") (pinfunction "2_2") (pintype "passive"))
    )
    (net (code "73") (name "Net-(J3-3)") (class "Default")
      (node (ref "J3") (pin "P$2") (pinfunction "3_P$2") (pintype "passive"))
      (node (ref "R16") (pin "1") (pinfunction "1_1") (pintype "passive"))
    )
    (net (code "74") (name "Net-(J4-2)") (class "Default")
      (node (ref "J4") (pin "P$1") (pinfunction "2_P$1") (pintype "passive"))
      (node (ref "R25") (pin "2") (pinfunction "2_2") (pintype "passive"))
    )
    (net (code "75") (name "Net-(J5-2)") (class "Default")
      (node (ref "J5") (pin "P$1") (pinfunction "2_P$1") (pintype "passive"))
      (node (ref "R22") (pin "1") (pinfunction "1_1") (pintype "passive"))
    )
    (net (code "76") (name "Net-(J5-3)") (class "Default")
      (node (ref "J5") (pin "P$2") (pinfunction "3_P$2") (pintype "passive"))
      (node (ref "R34") (pin "2") (pinfunction "2_2") (pintype "passive"))
    )
    (net (code "77") (name "Net-(J6-2)") (class "Default")
      (node (ref "J6") (pin "P$1") (pinfunction "2_P$1") (pintype "passive"))
      (node (ref "R37") (pin "2") (pinfunction "2_2") (pintype "passive"))
    )
    (net (code "78") (name "Net-(J6-3)") (class "Default")
      (node (ref "J6") (pin "P$2") (pinfunction "3_P$2") (pintype "passive"))
      (node (ref "R39") (pin "1") (pinfunction "1_1") (pintype "passive"))
    )
    (net (code "79") (name "Net-(J7-2)") (class "Default")
      (node (ref "J7") (pin "P$1") (pinfunction "2_P$1") (pintype "passive"))
      (node (ref "R54") (pin "2") (pinfunction "2_2") (pintype "passive"))
    )
    (net (code "80") (name "Net-(J8-2)") (class "Default")
      (node (ref "J8") (pin "P$1") (pinfunction "2_P$1") (pintype "passive"))
      (node (ref "R41") (pin "1") (pinfunction "1_1") (pintype "passive"))
    )
    (net (code "81") (name "Net-(J8-3)") (class "Default")
      (node (ref "J8") (pin "P$2") (pinfunction "3_P$2") (pintype "passive"))
      (node (ref "R44") (pin "2") (pinfunction "2_2") (pintype "passive"))
    )
    (net (code "82") (name "Net-(J9-2)") (class "Default")
      (node (ref "J9") (pin "P$1") (pinfunction "2_P$1") (pintype "passive"))
      (node (ref "R51") (pin "2") (pinfunction "2_2") (pintype "passive"))
    )
    (net (code "83") (name "Net-(J9-3)") (class "Default")
      (node (ref "J9") (pin "P$2") (pinfunction "3_P$2") (pintype "passive"))
      (node (ref "R56") (pin "1") (pinfunction "1_1") (pintype "passive"))
    )
    (net (code "84") (name "Net-(J10-2)") (class "Default")
      (node (ref "J10") (pin "P$1") (pinfunction "2_P$1") (pintype "passive"))
      (node (ref "R66") (pin "2") (pinfunction "2_2") (pintype "passive"))
    )
    (net (code "85") (name "Net-(J11-2)") (class "Default")
      (node (ref "J11") (pin "P$1") (pinfunction "2_P$1") (pintype "passive"))
      (node (ref "R62") (pin "1") (pinfunction "1_1") (pintype "passive"))
    )
    (net (code "86") (name "Net-(J12-2)") (class "Default")
      (node (ref "J12") (pin "P$1") (pinfunction "2_P$1") (pintype "passive"))
      (node (ref "R79") (pin "2") (pinfunction "2_2") (pintype "passive"))
    )
    (net (code "87") (name "Net-(J12-3)") (class "Default")
      (node (ref "J12") (pin "P$2") (pinfunction "3_P$2") (pintype "passive"))
      (node (ref "R72") (pin "1") (pinfunction "1_1") (pintype "passive"))
    )
    (net (code "88") (name "Net-(JP5-Pad10)") (class "Default")
      (node (ref "JP5") (pin "10") (pinfunction "10_10") (pintype "passive"))
      (node (ref "JP5") (pin "9") (pinfunction "9_9") (pintype "passive"))
      (node (ref "P1") (pin "2") (pinfunction "2_2") (pintype "bidirectional"))
    )
    (net (code "89") (name "Net-(L1-Pad2)") (class "Default")
      (node (ref "L1") (pin "2") (pinfunction "2_2") (pintype "passive"))
      (node (ref "P1") (pin "1") (pinfunction "1_1") (pintype "bidirectional"))
    )
    (net (code "90") (name "Net-(R1-A)") (class "Default")
      (node (ref "R1") (pin "P$3") (pinfunction "A_P$3") (pintype "passive"))
      (node (ref "R8") (pin "2") (pinfunction "2_2") (pintype "passive"))
    )
    (net (code "91") (name "Net-(R3-S)") (class "Default")
      (node (ref "R11") (pin "1") (pinfunction "1_1") (pintype "passive"))
      (node (ref "R3") (pin "P$2") (pinfunction "S_P$2") (pintype "passive"))
    )
    (net (code "92") (name "Net-(R28-A)") (class "Default")
      (node (ref "R28") (pin "P$3") (pinfunction "A_P$3") (pintype "passive"))
      (node (ref "R35") (pin "2") (pinfunction "2_2") (pintype "passive"))
    )
    (net (code "93") (name "Net-(R29-S)") (class "Default")
      (node (ref "R29") (pin "P$2") (pinfunction "S_P$2") (pintype "passive"))
      (node (ref "R37") (pin "1") (pinfunction "1_1") (pintype "passive"))
    )
    (net (code "94") (name "Net-(R40-A)") (class "Default")
      (node (ref "R40") (pin "P$3") (pinfunction "A_P$3") (pintype "passive"))
      (node (ref "R47") (pin "2") (pinfunction "2_2") (pintype "passive"))
    )
    (net (code "95") (name "Net-(R42-S)") (class "Default")
      (node (ref "R42") (pin "P$2") (pinfunction "S_P$2") (pintype "passive"))
      (node (ref "R51") (pin "1") (pinfunction "1_1") (pintype "passive"))
    )
    (net (code "96") (name "Net-(R69-A)") (class "Default")
      (node (ref "R69") (pin "P$3") (pinfunction "A_P$3") (pintype "passive"))
      (node (ref "R77") (pin "2") (pinfunction "2_2") (pintype "passive"))
    )
    (net (code "97") (name "Net-(R70-S)") (class "Default")
      (node (ref "R70") (pin "P$2") (pinfunction "S_P$2") (pintype "passive"))
      (node (ref "R79") (pin "1") (pinfunction "1_1") (pintype "passive"))
    )
    (net (code "98") (name "VCC") (class "Default")
      (node (ref "C19") (pin "1") (pinfunction "1_1") (pintype "passive"))
      (node (ref "C2") (pin "+") (pinfunction "+_+") (pintype "passive"))
      (node (ref "C21") (pin "+") (pinfunction "+_+") (pintype "passive"))
      (node (ref "C24") (pin "1") (pinfunction "1_1") (pintype "passive"))
      (node (ref "C27") (pin "1") (pinfunction "1_1") (pintype "passive"))
      (node (ref "C28") (pin "1") (pinfunction "1_1") (pintype "passive"))
      (node (ref "C4") (pin "1") (pinfunction "1_1") (pintype "passive"))
      (node (ref "C40") (pin "1") (pinfunction "1_1") (pintype "passive"))
      (node (ref "C7") (pin "1") (pinfunction "1_1") (pintype "passive"))
      (node (ref "C8") (pin "1") (pinfunction "1_1") (pintype "passive"))
      (node (ref "IC1") (pin "4") (pinfunction "V+_4") (pintype "power_in"))
      (node (ref "IC10") (pin "4") (pinfunction "V+_4") (pintype "power_in"))
      (node (ref "IC2") (pin "8") (pinfunction "V+_8") (pintype "power_in"))
      (node (ref "IC3") (pin "16") (pinfunction "V+_16") (pintype "power_in"))
      (node (ref "IC4") (pin "4") (pinfunction "V+_4") (pintype "power_in"))
      (node (ref "IC5") (pin "4") (pinfunction "V+_4") (pintype "power_in"))
      (node (ref "IC6") (pin "8") (pinfunction "V+_8") (pintype "power_in"))
      (node (ref "IC7") (pin "16") (pinfunction "V+_16") (pintype "power_in"))
      (node (ref "L2") (pin "1") (pinfunction "1_1") (pintype "passive"))
      (node (ref "R74") (pin "1") (pinfunction "1_1") (pintype "passive"))
    )
    (net (code "99") (name "VEE") (class "Default")
      (node (ref "C1") (pin "-") (pinfunction "-_-") (pintype "passive"))
      (node (ref "C11") (pin "2") (pinfunction "2_2") (pintype "passive"))
      (node (ref "C15") (pin "2") (pinfunction "2_2") (pintype "passive"))
      (node (ref "C20") (pin "2") (pinfunction "2_2") (pintype "passive"))
      (node (ref "C22") (pin "-") (pinfunction "-_-") (pintype "passive"))
      (node (ref "C23") (pin "2") (pinfunction "2_2") (pintype "passive"))
      (node (ref "C3") (pin "2") (pinfunction "2_2") (pintype "passive"))
      (node (ref "C31") (pin "2") (pinfunction "2_2") (pintype "passive"))
      (node (ref "C35") (pin "2") (pinfunction "2_2") (pintype "passive"))
      (node (ref "C39") (pin "2") (pinfunction "2_2") (pintype "passive"))
      (node (ref "D1") (pin "A") (pinfunction "A_A") (pintype "passive"))
      (node (ref "IC1") (pin "11") (pinfunction "V-_11") (pintype "power_in"))
      (node (ref "IC10") (pin "11") (pinfunction "V-_11") (pintype "power_in"))
      (node (ref "IC2") (pin "4") (pinfunction "V-_4") (pintype "power_in"))
      (node (ref "IC3") (pin "9") (pinfunction "V-_9") (pintype "power_in"))
      (node (ref "IC4") (pin "11") (pinfunction "V-_11") (pintype "power_in"))
      (node (ref "IC5") (pin "11") (pinfunction "V-_11") (pintype "power_in"))
      (node (ref "IC6") (pin "4") (pinfunction "V-_4") (pintype "power_in"))
      (node (ref "IC7") (pin "9") (pinfunction "V-_9") (pintype "power_in"))
      (node (ref "L1") (pin "1") (pinfunction "1_1") (pintype "passive"))
      (node (ref "R64") (pin "1") (pinfunction "1_1") (pintype "passive"))
    )
    (net (code "100") (name "unconnected-(IC3E-MODE-Pad1)") (class "Default")
      (node (ref "IC3") (pin "1") (pinfunction "MODE_1") (pintype "input"))
    )
    (net (code "101") (name "unconnected-(IC7E-MODE-Pad1)") (class "Default")
      (node (ref "IC7") (pin "1") (pinfunction "MODE_1") (pintype "input"))
    )
    (net (code "102") (name "unconnected-(J11-3-PadP$2)") (class "Default")
      (node (ref "J11") (pin "P$2") (pinfunction "3_P$2") (pintype "passive"))
    )
  )
)
